# elasticNode.net
KiCad netlist of a schematic drawn in EAGLE
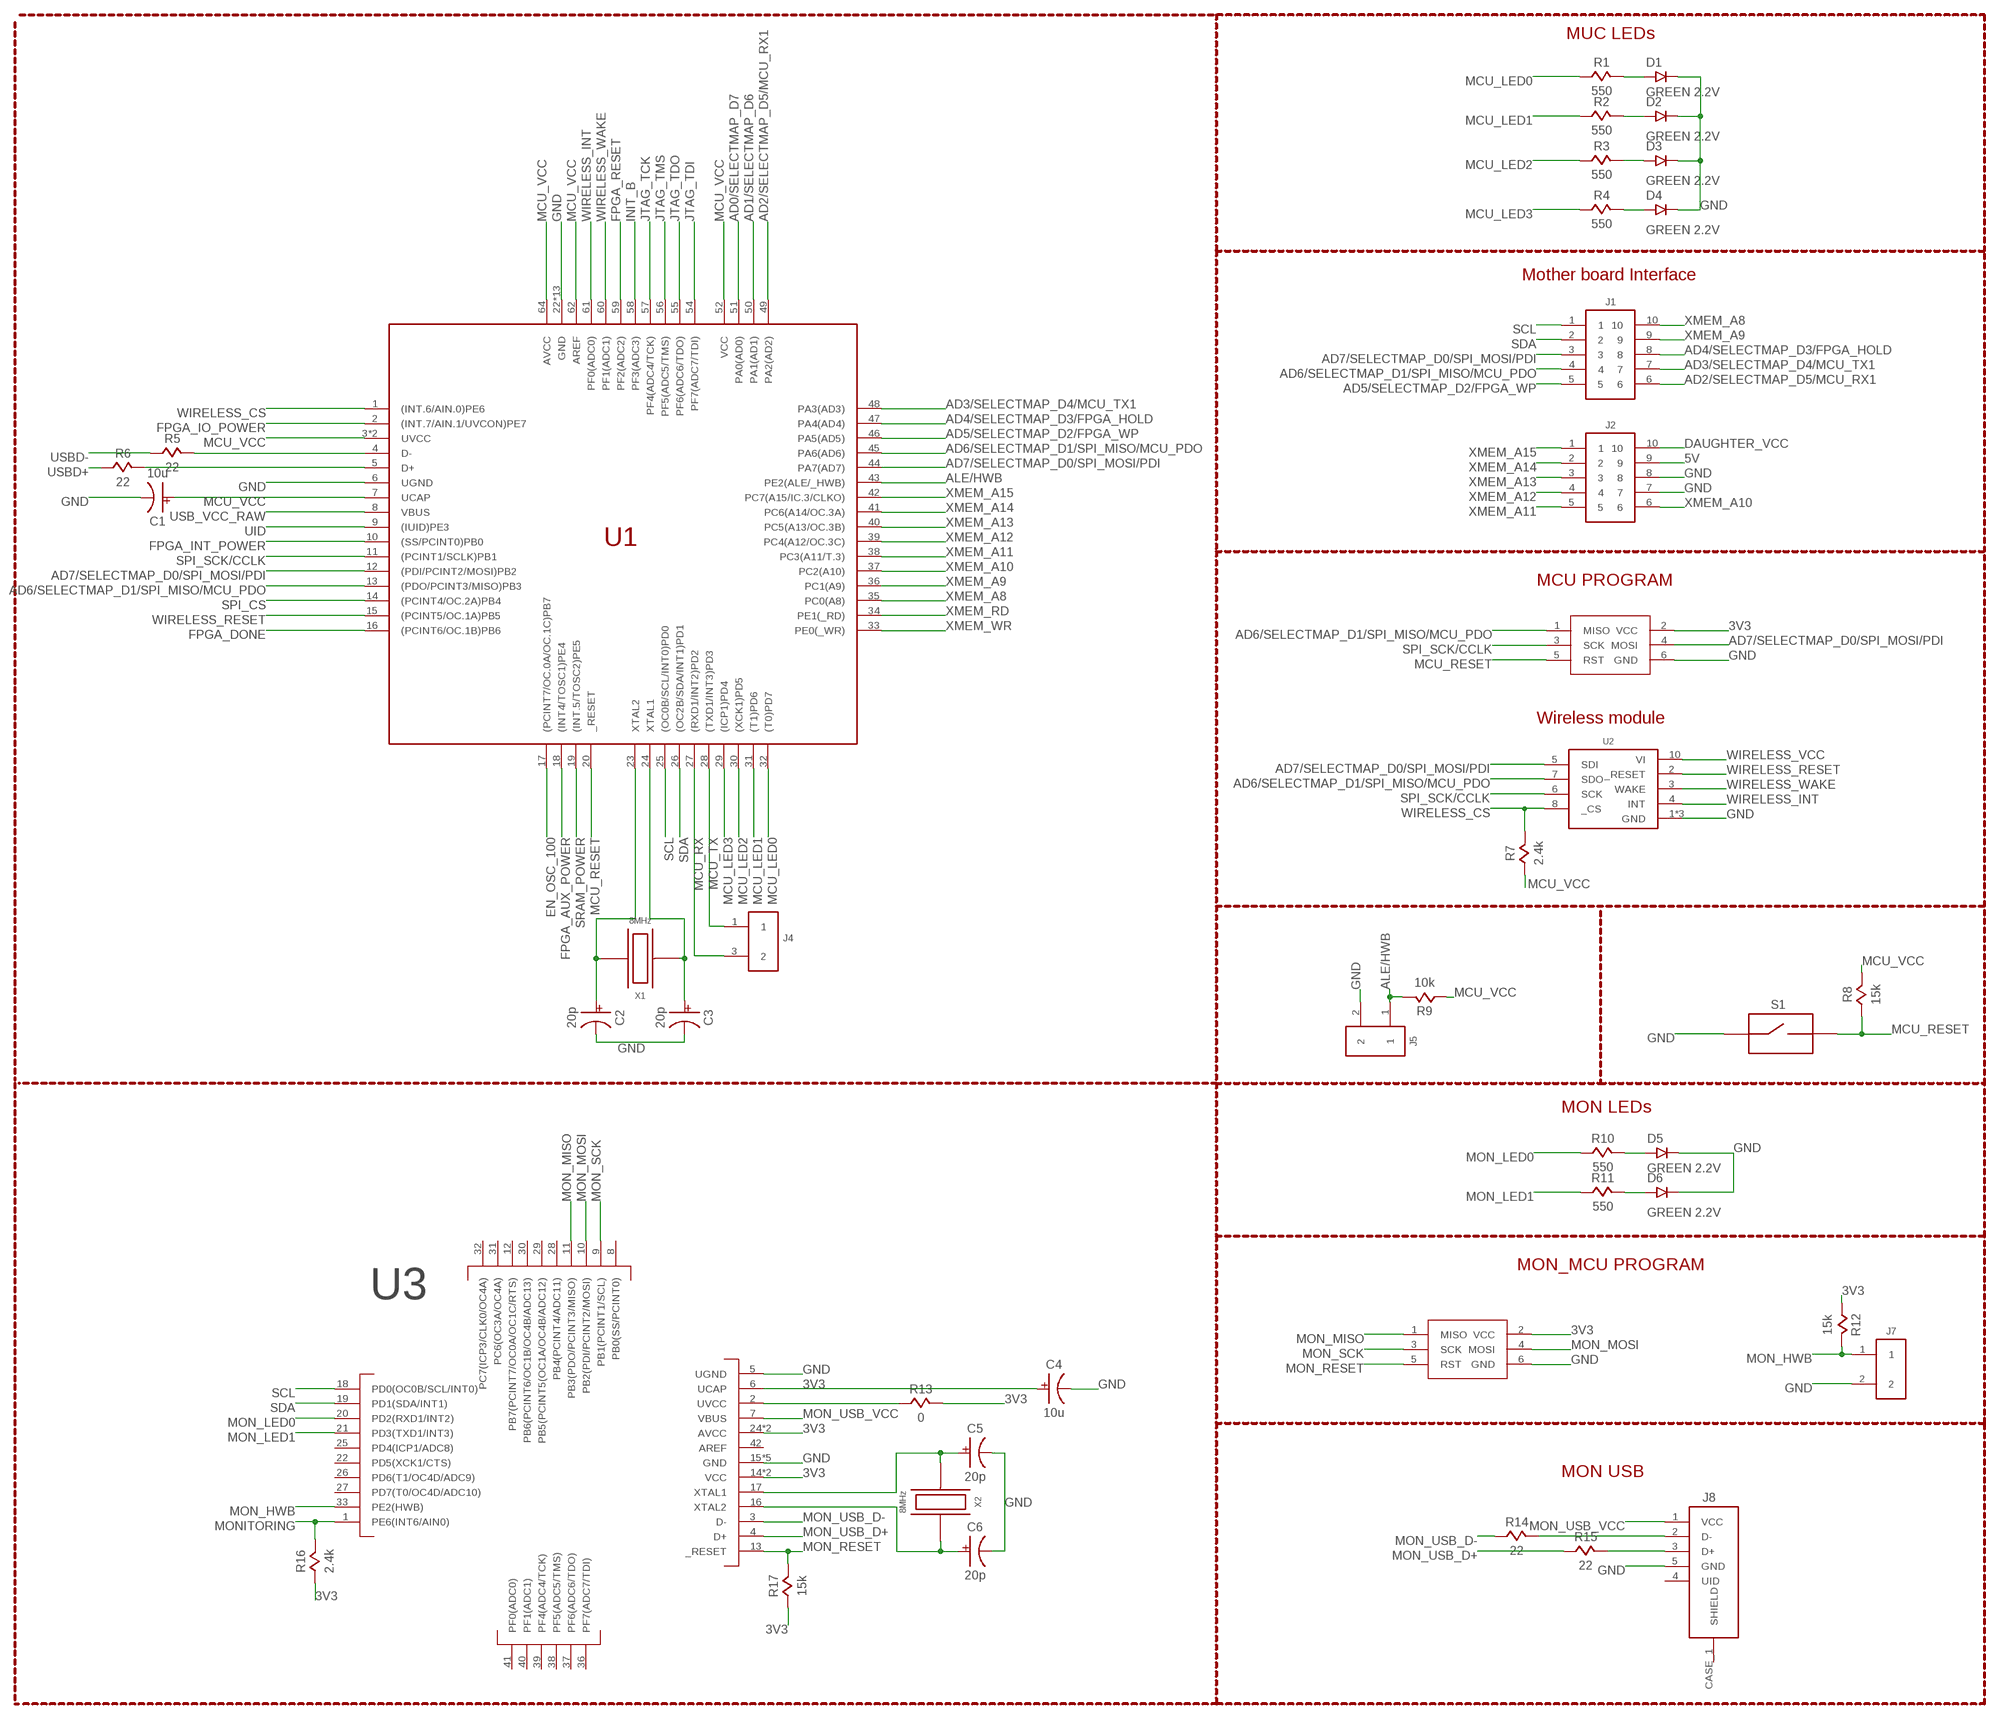
[diagram p0: schematic, sheet 1]
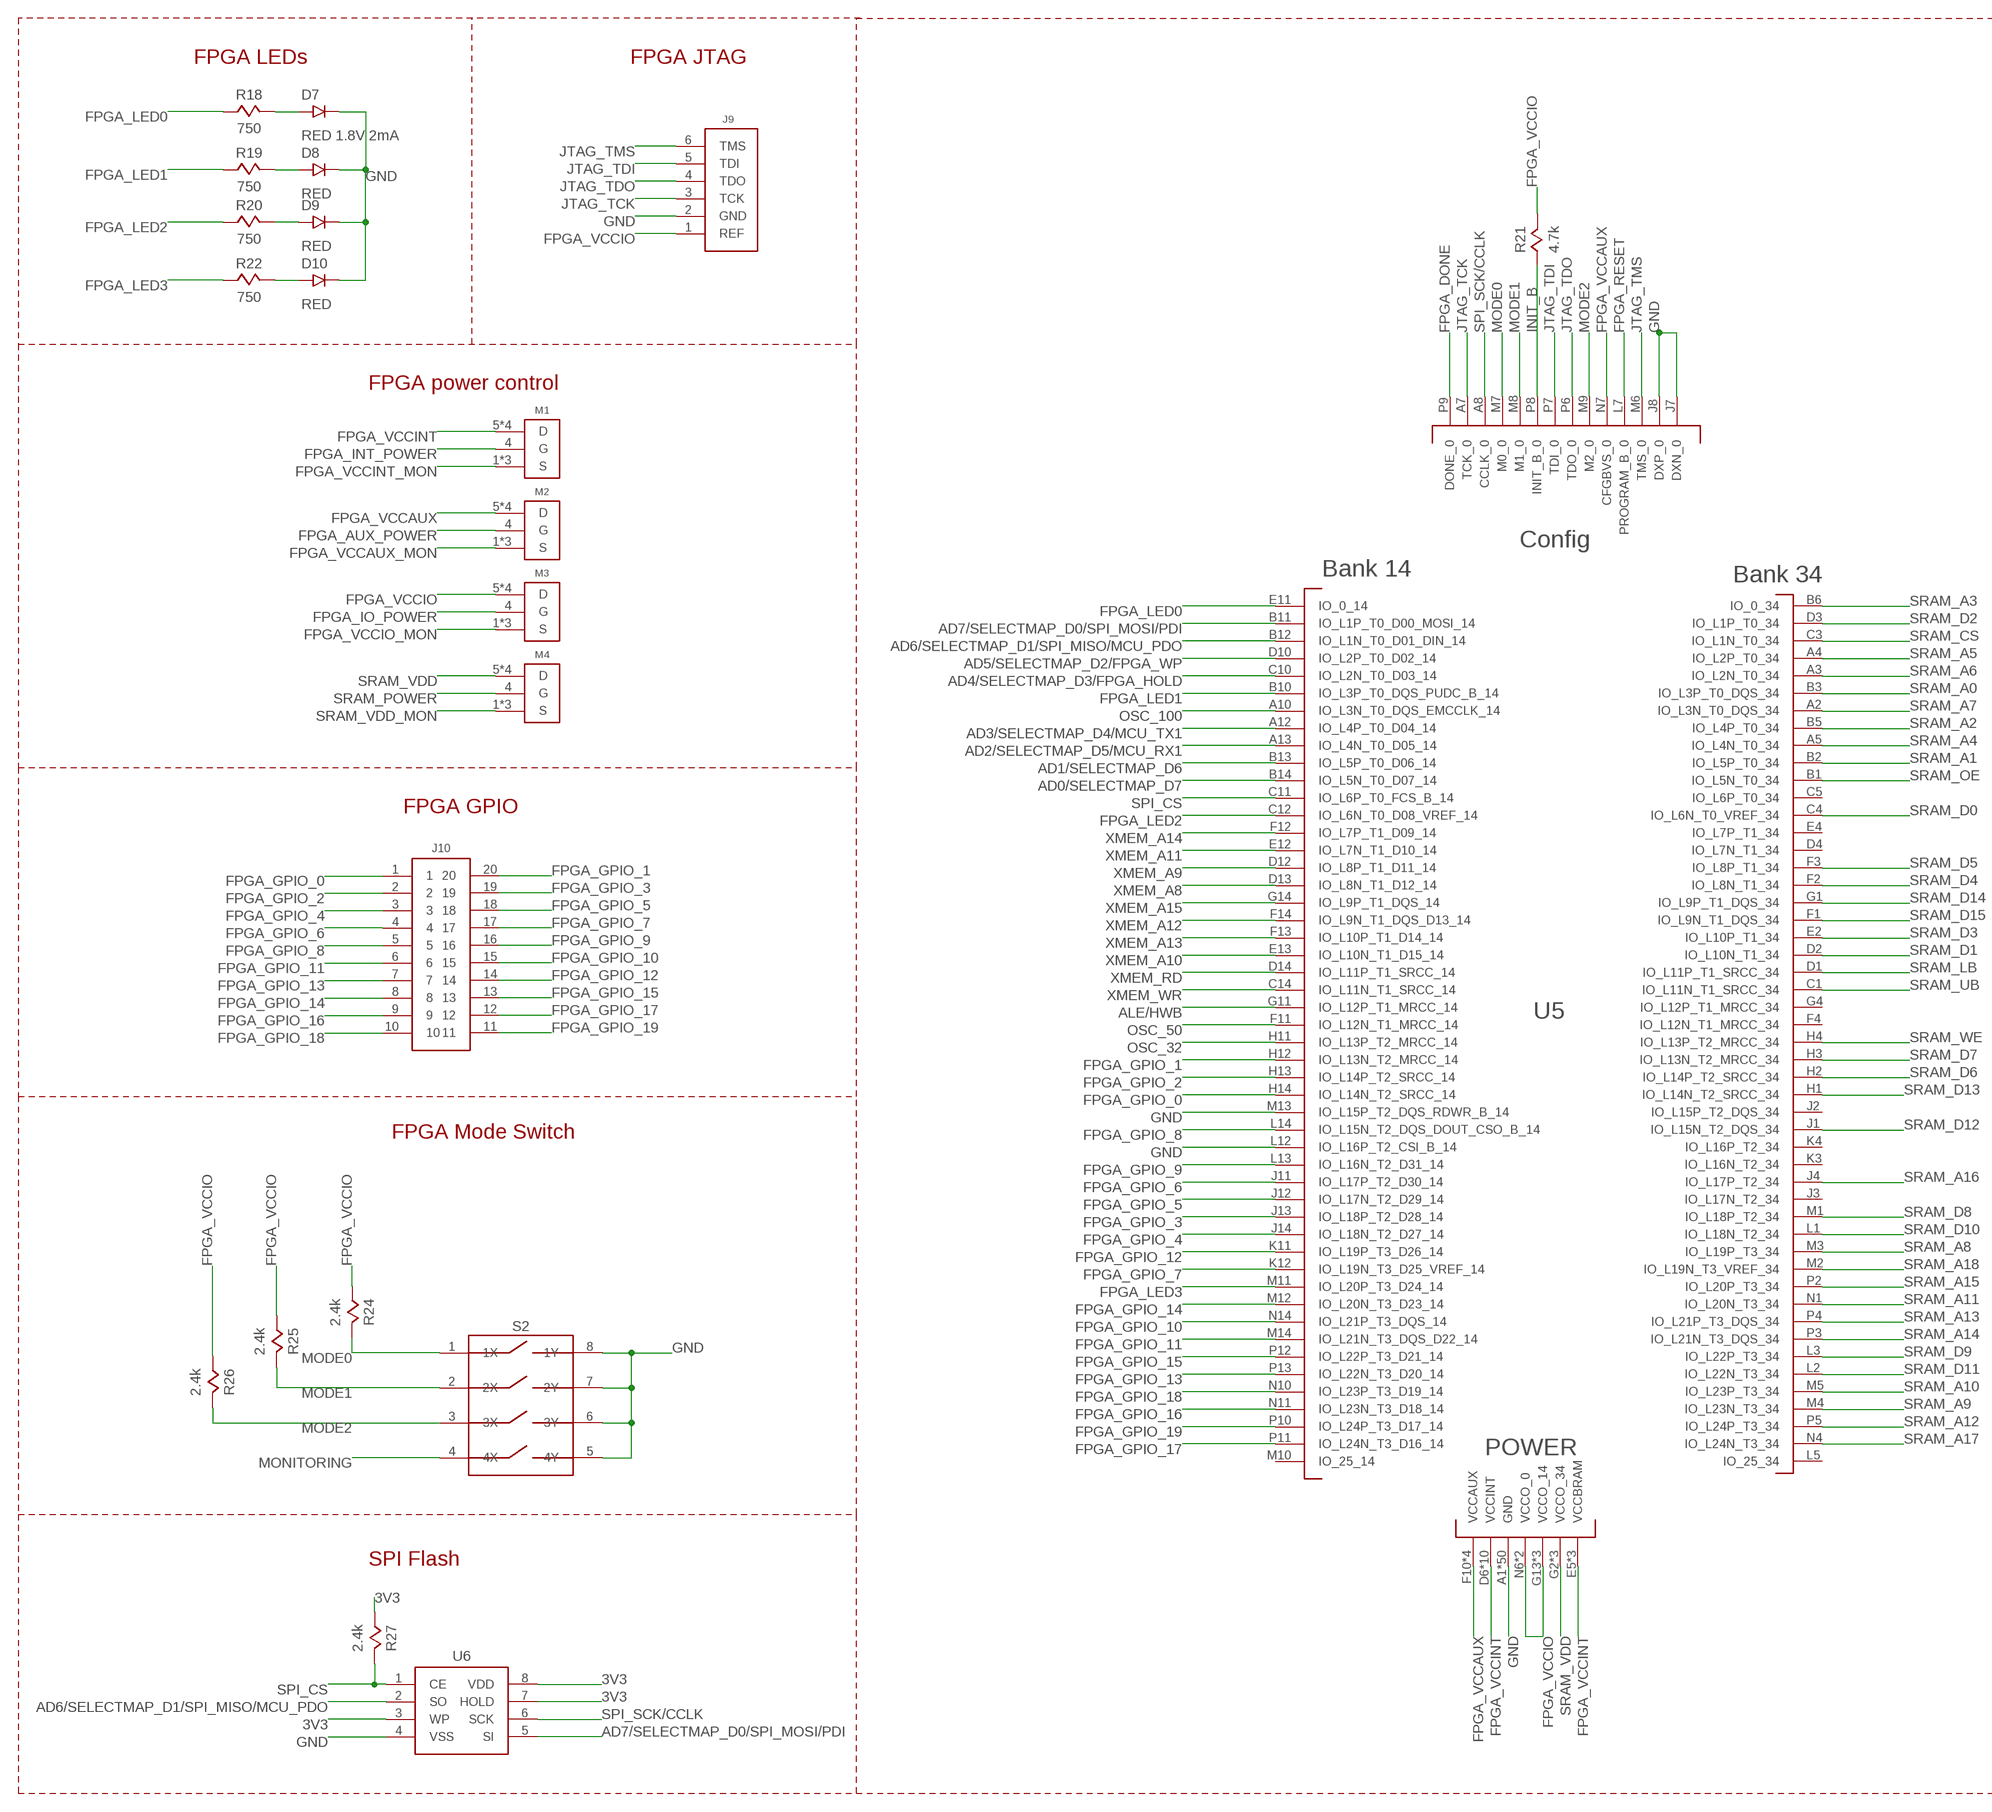
[diagram p1: schematic, sheet 2, part 1 of 2]
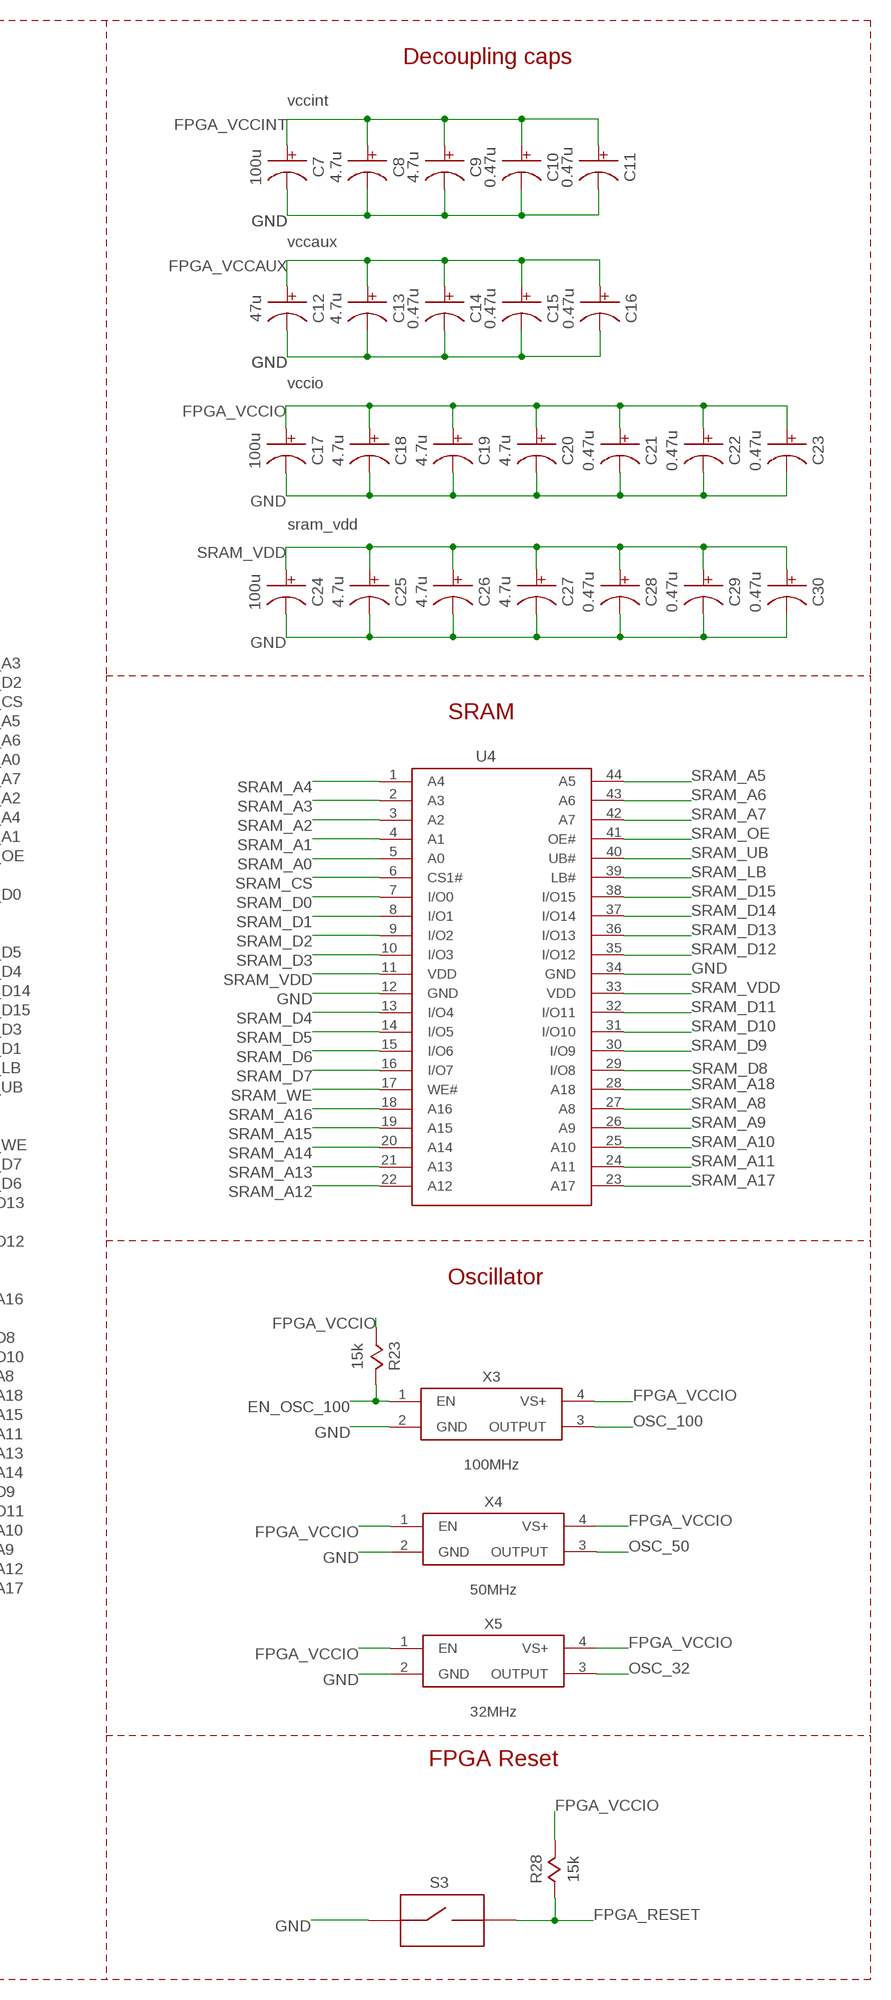
[diagram p2: schematic, sheet 2, part 2 of 2]
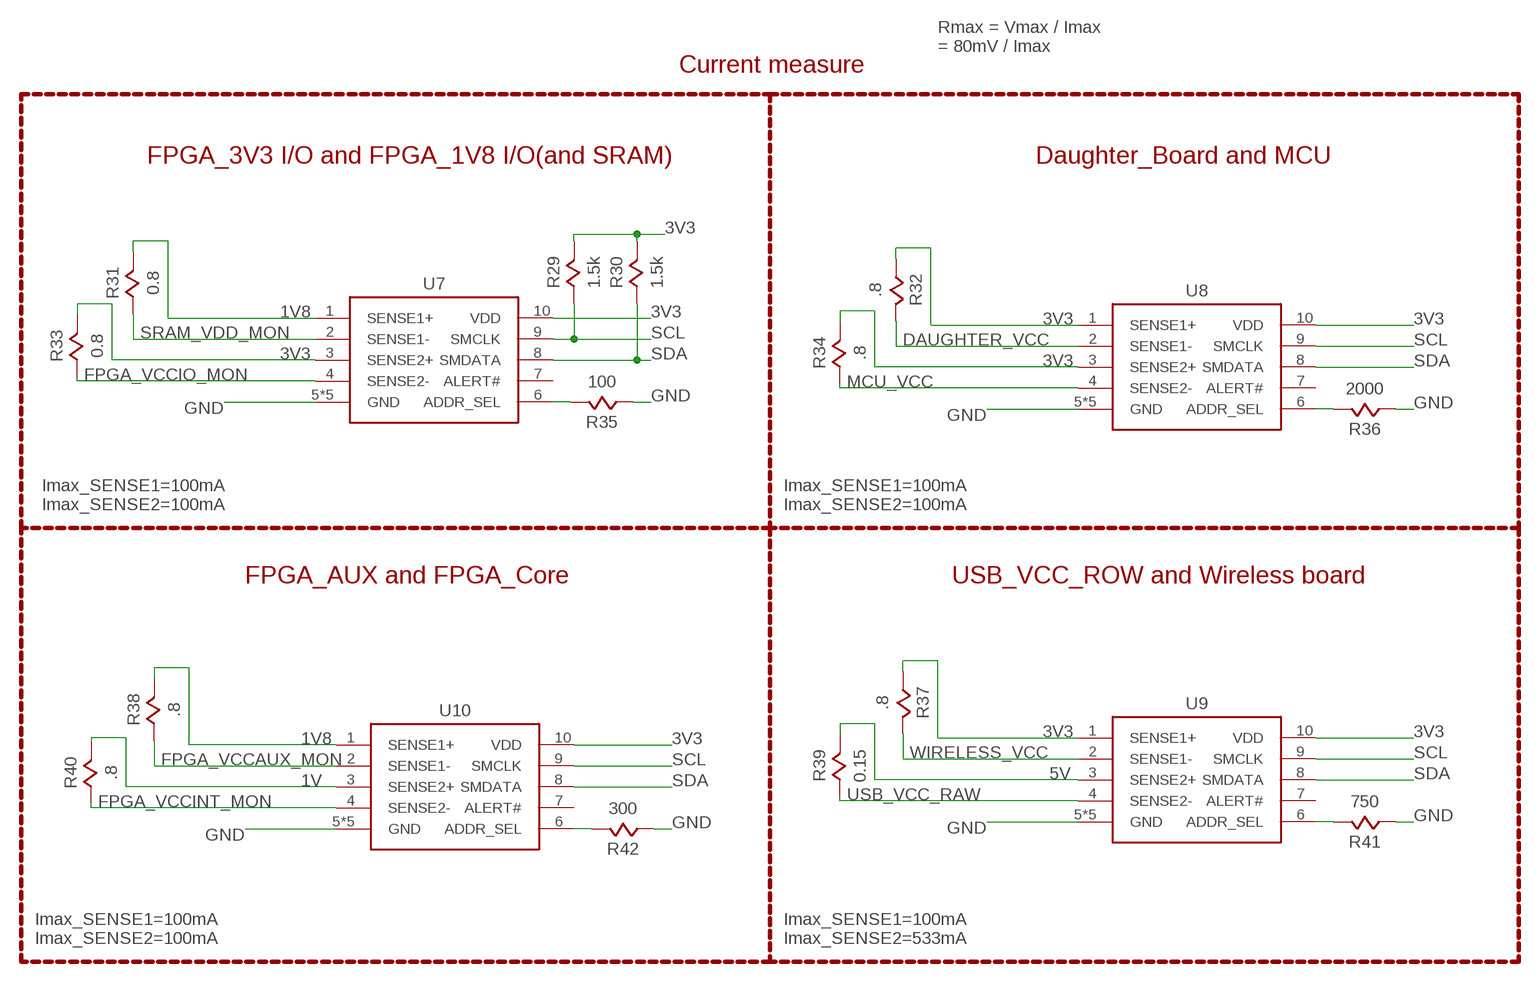
[diagram p3: schematic, sheet 3]
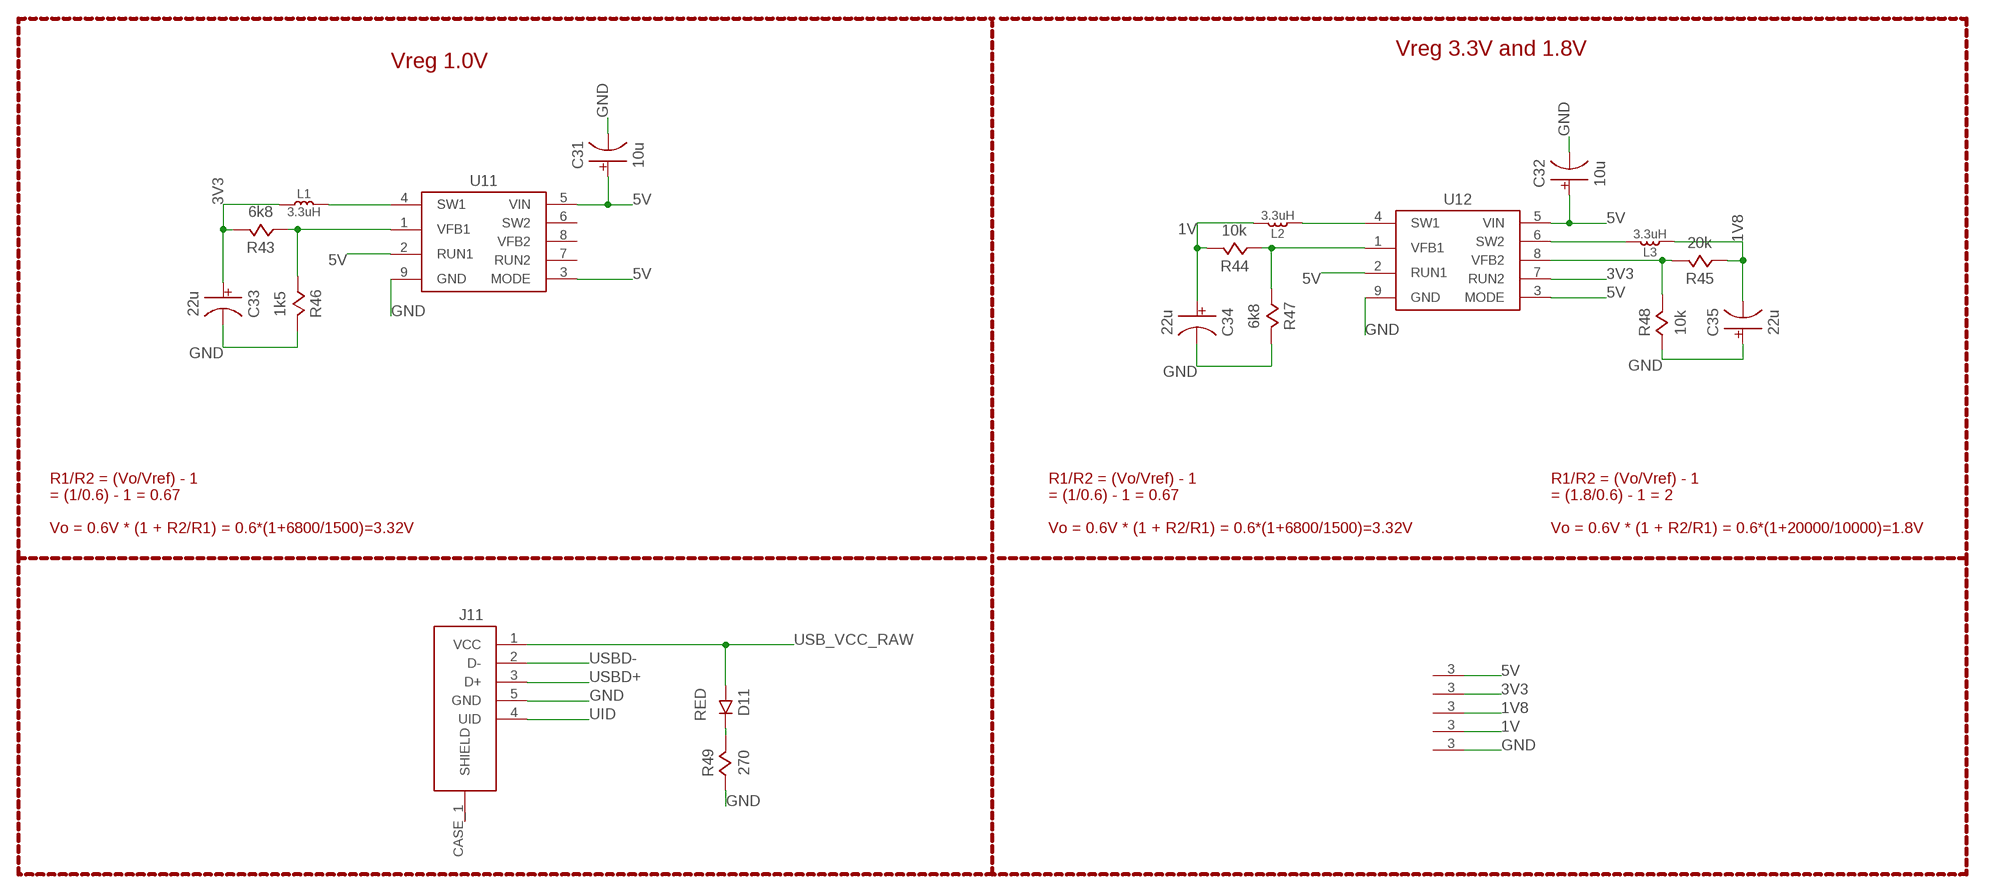
[diagram p4: schematic, sheet 4]

(export (version "E")
  (design (tool "Eeschema 10.0.6"))
  (components
    (comp (ref "C7")
      (value "100u")
      (footprint "eagle-import:1210")
      (libsource (lib "eagle-import") (part "CAPACITOR1210"))
    )
    (comp (ref "C8")
      (value "4.7u")
      (footprint "eagle-import:0805")
      (libsource (lib "eagle-import") (part "CAPACITOR0805"))
    )
    (comp (ref "C9")
      (value "4.7u")
      (footprint "eagle-import:0805")
      (libsource (lib "eagle-import") (part "CAPACITOR0805"))
    )
    (comp (ref "C10")
      (value "0.47u")
      (footprint "eagle-import:0805")
      (libsource (lib "eagle-import") (part "CAPACITOR0805"))
    )
    (comp (ref "C11")
      (value "0.47u")
      (footprint "eagle-import:0805")
      (libsource (lib "eagle-import") (part "CAPACITOR0805"))
    )
    (comp (ref "C12")
      (value "47u")
      (footprint "eagle-import:1210")
      (libsource (lib "eagle-import") (part "CAPACITOR1210"))
    )
    (comp (ref "C13")
      (value "4.7u")
      (footprint "eagle-import:0805")
      (libsource (lib "eagle-import") (part "CAPACITOR0805"))
    )
    (comp (ref "C14")
      (value "0.47u")
      (footprint "eagle-import:0805")
      (libsource (lib "eagle-import") (part "CAPACITOR0805"))
    )
    (comp (ref "C15")
      (value "0.47u")
      (footprint "eagle-import:0805")
      (libsource (lib "eagle-import") (part "CAPACITOR0805"))
    )
    (comp (ref "C16")
      (value "0.47u")
      (footprint "eagle-import:0805")
      (libsource (lib "eagle-import") (part "CAPACITOR0805"))
    )
    (comp (ref "C17")
      (value "100u")
      (footprint "eagle-import:1210")
      (libsource (lib "eagle-import") (part "CAPACITOR1210"))
    )
    (comp (ref "C18")
      (value "4.7u")
      (footprint "eagle-import:0805")
      (libsource (lib "eagle-import") (part "CAPACITOR0805"))
    )
    (comp (ref "C19")
      (value "4.7u")
      (footprint "eagle-import:0805")
      (libsource (lib "eagle-import") (part "CAPACITOR0805"))
    )
    (comp (ref "C20")
      (value "4.7u")
      (footprint "eagle-import:0805")
      (libsource (lib "eagle-import") (part "CAPACITOR0805"))
    )
    (comp (ref "C21")
      (value "0.47u")
      (footprint "eagle-import:0805")
      (libsource (lib "eagle-import") (part "CAPACITOR0805"))
    )
    (comp (ref "C22")
      (value "0.47u")
      (footprint "eagle-import:0805")
      (libsource (lib "eagle-import") (part "CAPACITOR0805"))
    )
    (comp (ref "C23")
      (value "0.47u")
      (footprint "eagle-import:0805")
      (libsource (lib "eagle-import") (part "CAPACITOR0805"))
    )
    (comp (ref "C24")
      (value "100u")
      (footprint "eagle-import:1210")
      (libsource (lib "eagle-import") (part "CAPACITOR1210"))
    )
    (comp (ref "C25")
      (value "4.7u")
      (footprint "eagle-import:0805")
      (libsource (lib "eagle-import") (part "CAPACITOR0805"))
    )
    (comp (ref "C26")
      (value "4.7u")
      (footprint "eagle-import:0805")
      (libsource (lib "eagle-import") (part "CAPACITOR0805"))
    )
    (comp (ref "C27")
      (value "4.7u")
      (footprint "eagle-import:0805")
      (libsource (lib "eagle-import") (part "CAPACITOR0805"))
    )
    (comp (ref "C28")
      (value "0.47u")
      (footprint "eagle-import:0805")
      (libsource (lib "eagle-import") (part "CAPACITOR0805"))
    )
    (comp (ref "C29")
      (value "0.47u")
      (footprint "eagle-import:0805")
      (libsource (lib "eagle-import") (part "CAPACITOR0805"))
    )
    (comp (ref "C30")
      (value "0.47u")
      (footprint "eagle-import:0805")
      (libsource (lib "eagle-import") (part "CAPACITOR0805"))
    )
    (comp (ref "D7")
      (value "RED 1.8V 2mA")
      (footprint "eagle-import:0805")
      (libsource (lib "eagle-import") (part "LED"))
    )
    (comp (ref "D8")
      (value "RED")
      (footprint "eagle-import:0805")
      (libsource (lib "eagle-import") (part "LED"))
    )
    (comp (ref "D9")
      (value "RED")
      (footprint "eagle-import:0805")
      (libsource (lib "eagle-import") (part "LED"))
    )
    (comp (ref "D10")
      (value "RED")
      (footprint "eagle-import:0805")
      (libsource (lib "eagle-import") (part "LED"))
    )
    (comp (ref "J9")
      (value "JTAG_CONN_6PINSMT")
      (footprint "eagle-import:6X1_JTAG")
      (libsource (lib "eagle-import") (part "JTAG_CONN_6PINSMT"))
    )
    (comp (ref "J10")
      (value "FEMALE_HEADER_10X2")
      (footprint "eagle-import:10X2_HEADER_SMT")
      (libsource (lib "eagle-import") (part "FEMALE_HEADER_10X2"))
    )
    (comp (ref "M1")
      (value "SISS23DN")
      (footprint "eagle-import:POWERPAK1212-8")
      (libsource (lib "eagle-import") (part "SISS23DN"))
    )
    (comp (ref "M2")
      (value "SISS23DN")
      (footprint "eagle-import:POWERPAK1212-8")
      (libsource (lib "eagle-import") (part "SISS23DN"))
    )
    (comp (ref "M3")
      (value "SISS23DN")
      (footprint "eagle-import:POWERPAK1212-8")
      (libsource (lib "eagle-import") (part "SISS23DN"))
    )
    (comp (ref "M4")
      (value "SISS23DN")
      (footprint "eagle-import:POWERPAK1212-8")
      (libsource (lib "eagle-import") (part "SISS23DN"))
    )
    (comp (ref "R18")
      (value "750")
      (footprint "eagle-import:0805")
      (libsource (lib "eagle-import") (part "RESISTOR"))
    )
    (comp (ref "R19")
      (value "750")
      (footprint "eagle-import:0805")
      (libsource (lib "eagle-import") (part "RESISTOR"))
    )
    (comp (ref "R20")
      (value "750")
      (footprint "eagle-import:0805")
      (libsource (lib "eagle-import") (part "RESISTOR"))
    )
    (comp (ref "R21")
      (value "4.7k")
      (footprint "eagle-import:0805")
      (libsource (lib "eagle-import") (part "RESISTOR"))
    )
    (comp (ref "R22")
      (value "750")
      (footprint "eagle-import:0805")
      (libsource (lib "eagle-import") (part "RESISTOR"))
    )
    (comp (ref "R23")
      (value "15k")
      (footprint "eagle-import:0805")
      (libsource (lib "eagle-import") (part "RESISTOR"))
    )
    (comp (ref "R24")
      (value "2.4k")
      (footprint "eagle-import:0805")
      (libsource (lib "eagle-import") (part "RESISTOR"))
    )
    (comp (ref "R25")
      (value "2.4k")
      (footprint "eagle-import:0805")
      (libsource (lib "eagle-import") (part "RESISTOR"))
    )
    (comp (ref "R26")
      (value "2.4k")
      (footprint "eagle-import:0805")
      (libsource (lib "eagle-import") (part "RESISTOR"))
    )
    (comp (ref "R27")
      (value "2.4k")
      (footprint "eagle-import:0805")
      (libsource (lib "eagle-import") (part "RESISTOR"))
    )
    (comp (ref "R28")
      (value "15k")
      (footprint "eagle-import:0805")
      (libsource (lib "eagle-import") (part "RESISTOR"))
    )
    (comp (ref "S2")
      (value "SPST_DIP_4")
      (footprint "eagle-import:SPST_DIP4_SMT")
      (libsource (lib "eagle-import") (part "SPST_DIP_4"))
    )
    (comp (ref "S3")
      (value "SPST_BUTTON2PIN_SMT")
      (footprint "eagle-import:SPST_2PIN_SMT")
      (libsource (lib "eagle-import") (part "SPST_BUTTON2PIN_SMT"))
    )
    (comp (ref "U4")
      (value "IS66WV51216EALL")
      (footprint "eagle-import:TSOP44")
      (libsource (lib "eagle-import") (part "IS66WV51216EALL"))
    )
    (comp (ref "U5")
      (value "SPARTAN7-LX15")
      (footprint "eagle-import:FTGB196")
      (libsource (lib "eagle-import") (part "SPARTAN7-LX15"))
    )
    (comp (ref "U6")
      (value "SST26VF032BWDFN")
      (footprint "eagle-import:WDFN8")
      (libsource (lib "eagle-import") (part "SST26VF032BWDFN"))
    )
    (comp (ref "X3")
      (value "100MHz")
      (footprint "eagle-import:3.2X2.5_OSC")
      (libsource (lib "eagle-import") (part "OSCILLATOR3.2X2.5"))
    )
    (comp (ref "X4")
      (value "50MHz")
      (footprint "eagle-import:3.2X2.5_OSC")
      (libsource (lib "eagle-import") (part "OSCILLATOR3.2X2.5"))
    )
    (comp (ref "X5")
      (value "32MHz")
      (footprint "eagle-import:3.2X2.5_OSC")
      (libsource (lib "eagle-import") (part "OSCILLATOR3.2X2.5"))
    )
    (comp (ref "R29")
      (value "1.5k")
      (footprint "eagle-import:0805")
      (libsource (lib "eagle-import") (part "RESISTOR"))
    )
    (comp (ref "R30")
      (value "1.5k")
      (footprint "eagle-import:0805")
      (libsource (lib "eagle-import") (part "RESISTOR"))
    )
    (comp (ref "R31")
      (value "0.8")
      (footprint "eagle-import:0805")
      (libsource (lib "eagle-import") (part "RESISTOR"))
    )
    (comp (ref "R32")
      (value ".8")
      (footprint "eagle-import:0805")
      (libsource (lib "eagle-import") (part "RESISTOR"))
    )
    (comp (ref "R33")
      (value "0.8")
      (footprint "eagle-import:0805")
      (libsource (lib "eagle-import") (part "RESISTOR"))
    )
    (comp (ref "R34")
      (value ".8")
      (footprint "eagle-import:0805")
      (libsource (lib "eagle-import") (part "RESISTOR"))
    )
    (comp (ref "R35")
      (value "100")
      (footprint "eagle-import:0805")
      (libsource (lib "eagle-import") (part "RESISTOR"))
    )
    (comp (ref "R36")
      (value "2000")
      (footprint "eagle-import:0805")
      (libsource (lib "eagle-import") (part "RESISTOR"))
    )
    (comp (ref "R37")
      (value ".8")
      (footprint "eagle-import:0805")
      (libsource (lib "eagle-import") (part "RESISTOR"))
    )
    (comp (ref "R38")
      (value ".8")
      (footprint "eagle-import:0805")
      (libsource (lib "eagle-import") (part "RESISTOR"))
    )
    (comp (ref "R39")
      (value "0.15")
      (footprint "eagle-import:0805")
      (libsource (lib "eagle-import") (part "RESISTOR"))
    )
    (comp (ref "R40")
      (value ".8")
      (footprint "eagle-import:0805")
      (libsource (lib "eagle-import") (part "RESISTOR"))
    )
    (comp (ref "R41")
      (value "750")
      (footprint "eagle-import:0805")
      (libsource (lib "eagle-import") (part "RESISTOR"))
    )
    (comp (ref "R42")
      (value "300")
      (footprint "eagle-import:0805")
      (libsource (lib "eagle-import") (part "RESISTOR"))
    )
    (comp (ref "U7")
      (value "PAC1720")
      (footprint "eagle-import:VDFN10")
      (libsource (lib "eagle-import") (part "PAC1720"))
    )
    (comp (ref "U8")
      (value "PAC1720")
      (footprint "eagle-import:VDFN10")
      (libsource (lib "eagle-import") (part "PAC1720"))
    )
    (comp (ref "U9")
      (value "PAC1720")
      (footprint "eagle-import:VDFN10")
      (libsource (lib "eagle-import") (part "PAC1720"))
    )
    (comp (ref "U10")
      (value "PAC1720")
      (footprint "eagle-import:VDFN10")
      (libsource (lib "eagle-import") (part "PAC1720"))
    )
    (comp (ref "C1")
      (value "10u")
      (footprint "eagle-import:0805")
      (libsource (lib "eagle-import") (part "CAPACITOR0805"))
    )
    (comp (ref "C2")
      (value "20p")
      (footprint "eagle-import:0805")
      (libsource (lib "eagle-import") (part "CAPACITOR0805"))
    )
    (comp (ref "C3")
      (value "20p")
      (footprint "eagle-import:0805")
      (libsource (lib "eagle-import") (part "CAPACITOR0805"))
    )
    (comp (ref "C4")
      (value "10u")
      (footprint "eagle-import:0805")
      (libsource (lib "eagle-import") (part "CAPACITOR0805"))
    )
    (comp (ref "C5")
      (value "20p")
      (footprint "eagle-import:0805")
      (libsource (lib "eagle-import") (part "CAPACITOR0805"))
    )
    (comp (ref "C6")
      (value "20p")
      (footprint "eagle-import:0805")
      (libsource (lib "eagle-import") (part "CAPACITOR0805"))
    )
    (comp (ref "D1")
      (value "GREEN 2.2V")
      (footprint "eagle-import:0805")
      (libsource (lib "eagle-import") (part "LED"))
    )
    (comp (ref "D2")
      (value "GREEN 2.2V")
      (footprint "eagle-import:0805")
      (libsource (lib "eagle-import") (part "LED"))
    )
    (comp (ref "D3")
      (value "GREEN 2.2V")
      (footprint "eagle-import:0805")
      (libsource (lib "eagle-import") (part "LED"))
    )
    (comp (ref "D4")
      (value "GREEN 2.2V")
      (footprint "eagle-import:0805")
      (libsource (lib "eagle-import") (part "LED"))
    )
    (comp (ref "D5")
      (value "GREEN 2.2V")
      (footprint "eagle-import:0805")
      (libsource (lib "eagle-import") (part "LED"))
    )
    (comp (ref "D6")
      (value "GREEN 2.2V")
      (footprint "eagle-import:0805")
      (libsource (lib "eagle-import") (part "LED"))
    )
    (comp (ref "J1")
      (value "FEMALE_HEADER_5X2")
      (footprint "eagle-import:5X2_HEADER_SMT_1.27")
      (libsource (lib "eagle-import") (part "FEMALE_HEADER_5X2"))
    )
    (comp (ref "J2")
      (value "FEMALE_HEADER_5X2")
      (footprint "eagle-import:5X2_HEADER_SMT_1.27")
      (libsource (lib "eagle-import") (part "FEMALE_HEADER_5X2"))
    )
    (comp (ref "J3")
      (value "ISP_CONN_6PIN")
      (footprint "eagle-import:ICSP_SMT")
      (fields (field (name "SPICEPREFIX") "X"))
      (libsource (lib "eagle-import") (part "ISP_CONN_6PIN"))
    )
    (comp (ref "J4")
      (value "FEMALE_HEADER_2X1")
      (footprint "eagle-import:2X1_HEADER")
      (libsource (lib "eagle-import") (part "FEMALE_HEADER_2X1"))
    )
    (comp (ref "J5")
      (value "JUMPER")
      (footprint "eagle-import:JUMPER_SMT")
      (libsource (lib "eagle-import") (part "JUMPER"))
    )
    (comp (ref "J6")
      (value "ISP_CONN_6PIN")
      (footprint "eagle-import:ICSP_SMT")
      (libsource (lib "eagle-import") (part "ISP_CONN_6PIN"))
    )
    (comp (ref "J7")
      (value "JUMPER")
      (footprint "eagle-import:JUMPER_SMT")
      (libsource (lib "eagle-import") (part "JUMPER"))
    )
    (comp (ref "J8")
      (value "USB_CONNMICRO_SMT")
      (footprint "eagle-import:USB_MICRO_B_SMT")
      (libsource (lib "eagle-import") (part "USB_CONNMICRO_SMT"))
    )
    (comp (ref "R1")
      (value "550")
      (footprint "eagle-import:0805")
      (libsource (lib "eagle-import") (part "RESISTOR"))
    )
    (comp (ref "R2")
      (value "550")
      (footprint "eagle-import:0805")
      (libsource (lib "eagle-import") (part "RESISTOR"))
    )
    (comp (ref "R3")
      (value "550")
      (footprint "eagle-import:0805")
      (libsource (lib "eagle-import") (part "RESISTOR"))
    )
    (comp (ref "R4")
      (value "550")
      (footprint "eagle-import:0805")
      (libsource (lib "eagle-import") (part "RESISTOR"))
    )
    (comp (ref "R5")
      (value "22")
      (footprint "eagle-import:0805")
      (libsource (lib "eagle-import") (part "RESISTOR"))
    )
    (comp (ref "R6")
      (value "22")
      (footprint "eagle-import:0805")
      (libsource (lib "eagle-import") (part "RESISTOR"))
    )
    (comp (ref "R7")
      (value "2.4k")
      (footprint "eagle-import:0805")
      (libsource (lib "eagle-import") (part "RESISTOR"))
    )
    (comp (ref "R8")
      (value "15k")
      (footprint "eagle-import:0805")
      (libsource (lib "eagle-import") (part "RESISTOR"))
    )
    (comp (ref "R9")
      (value "10k")
      (footprint "eagle-import:0805")
      (libsource (lib "eagle-import") (part "RESISTOR"))
    )
    (comp (ref "R10")
      (value "550")
      (footprint "eagle-import:0805")
      (libsource (lib "eagle-import") (part "RESISTOR"))
    )
    (comp (ref "R11")
      (value "550")
      (footprint "eagle-import:0805")
      (libsource (lib "eagle-import") (part "RESISTOR"))
    )
    (comp (ref "R12")
      (value "15k")
      (footprint "eagle-import:0805")
      (libsource (lib "eagle-import") (part "RESISTOR"))
    )
    (comp (ref "R13")
      (value "0")
      (footprint "eagle-import:0805")
      (libsource (lib "eagle-import") (part "RESISTOR"))
    )
    (comp (ref "R14")
      (value "22")
      (footprint "eagle-import:0805")
      (libsource (lib "eagle-import") (part "RESISTOR"))
    )
    (comp (ref "R15")
      (value "22")
      (footprint "eagle-import:0805")
      (libsource (lib "eagle-import") (part "RESISTOR"))
    )
    (comp (ref "R16")
      (value "2.4k")
      (footprint "eagle-import:0805")
      (libsource (lib "eagle-import") (part "RESISTOR"))
    )
    (comp (ref "R17")
      (value "15k")
      (footprint "eagle-import:0805")
      (libsource (lib "eagle-import") (part "RESISTOR"))
    )
    (comp (ref "S1")
      (value "SPST_BUTTON2PIN_SMT")
      (footprint "eagle-import:SPST_2PIN_SMT")
      (libsource (lib "eagle-import") (part "SPST_BUTTON2PIN_SMT"))
    )
    (comp (ref "U1")
      (value "AT90USB128")
      (footprint "eagle-import:QFN64")
      (libsource (lib "eagle-import") (part "AT90USB128"))
    )
    (comp (ref "U2")
      (value "MRF24J40MA")
      (footprint "eagle-import:MRF24J40MA")
      (libsource (lib "eagle-import") (part "MRF24J40MA"))
    )
    (comp (ref "U3")
      (value "ATMEGA32U4QFN")
      (footprint "eagle-import:QFN44")
      (libsource (lib "eagle-import") (part "ATMEGA32U4QFN"))
    )
    (comp (ref "X1")
      (value "8MHz")
      (footprint "eagle-import:3.2X2.5_OSC")
      (libsource (lib "eagle-import") (part "QUARTZ"))
    )
    (comp (ref "X2")
      (value "8MHz")
      (footprint "eagle-import:3.2X2.5_OSC")
      (libsource (lib "eagle-import") (part "QUARTZ"))
    )
    (comp (ref "C31")
      (value "10u")
      (footprint "eagle-import:0805")
      (libsource (lib "eagle-import") (part "CAPACITOR0805"))
    )
    (comp (ref "C32")
      (value "10u")
      (footprint "eagle-import:0805")
      (libsource (lib "eagle-import") (part "CAPACITOR0805"))
    )
    (comp (ref "C33")
      (value "22u")
      (footprint "eagle-import:0805")
      (libsource (lib "eagle-import") (part "CAPACITOR0805"))
    )
    (comp (ref "C34")
      (value "22u")
      (footprint "eagle-import:0805")
      (libsource (lib "eagle-import") (part "CAPACITOR0805"))
    )
    (comp (ref "C35")
      (value "22u")
      (footprint "eagle-import:0805")
      (libsource (lib "eagle-import") (part "CAPACITOR0805"))
    )
    (comp (ref "D11")
      (value "RED")
      (footprint "eagle-import:0805")
      (libsource (lib "eagle-import") (part "LED"))
    )
    (comp (ref "J11")
      (value "USB_CONNMICRO_SMT")
      (footprint "eagle-import:USB_MICRO_B_SMT")
      (libsource (lib "eagle-import") (part "USB_CONNMICRO_SMT"))
    )
    (comp (ref "L1")
      (value "3.3uH")
      (footprint "eagle-import:0805")
      (libsource (lib "eagle-import") (part "INDUCTOR"))
    )
    (comp (ref "L2")
      (value "3.3uH")
      (footprint "eagle-import:0805")
      (libsource (lib "eagle-import") (part "INDUCTOR"))
    )
    (comp (ref "L3")
      (value "3.3uH")
      (footprint "eagle-import:0805")
      (libsource (lib "eagle-import") (part "INDUCTOR"))
    )
    (comp (ref "R43")
      (value "6k8")
      (footprint "eagle-import:0805")
      (libsource (lib "eagle-import") (part "RESISTOR"))
    )
    (comp (ref "R44")
      (value "10k")
      (footprint "eagle-import:0805")
      (libsource (lib "eagle-import") (part "RESISTOR"))
    )
    (comp (ref "R45")
      (value "20k")
      (footprint "eagle-import:0805")
      (libsource (lib "eagle-import") (part "RESISTOR"))
    )
    (comp (ref "R46")
      (value "1k5")
      (footprint "eagle-import:0805")
      (libsource (lib "eagle-import") (part "RESISTOR"))
    )
    (comp (ref "R47")
      (value "6k8")
      (footprint "eagle-import:0805")
      (libsource (lib "eagle-import") (part "RESISTOR"))
    )
    (comp (ref "R48")
      (value "10k")
      (footprint "eagle-import:0805")
      (libsource (lib "eagle-import") (part "RESISTOR"))
    )
    (comp (ref "R49")
      (value "270")
      (footprint "eagle-import:0805")
      (libsource (lib "eagle-import") (part "RESISTOR"))
    )
    (comp (ref "TP1")
      (value "TEST_POINTTHT")
      (footprint "eagle-import:THT")
      (libsource (lib "eagle-import") (part "TEST_POINTTHT"))
    )
    (comp (ref "TP2")
      (value "TEST_POINTTHT")
      (footprint "eagle-import:THT")
      (libsource (lib "eagle-import") (part "TEST_POINTTHT"))
    )
    (comp (ref "TP3")
      (value "TEST_POINTTHT")
      (footprint "eagle-import:THT")
      (libsource (lib "eagle-import") (part "TEST_POINTTHT"))
    )
    (comp (ref "TP4")
      (value "TEST_POINTTHT")
      (footprint "eagle-import:THT")
      (libsource (lib "eagle-import") (part "TEST_POINTTHT"))
    )
    (comp (ref "TP5")
      (value "TEST_POINTTHT")
      (footprint "eagle-import:THT")
      (libsource (lib "eagle-import") (part "TEST_POINTTHT"))
    )
    (comp (ref "U11")
      (value "LTC3419DFN")
      (footprint "eagle-import:DFN8")
      (libsource (lib "eagle-import") (part "LTC3419DFN"))
    )
    (comp (ref "U12")
      (value "LTC3419DFN")
      (footprint "eagle-import:DFN8")
      (libsource (lib "eagle-import") (part "LTC3419DFN"))
    )
  )
  (nets
    (net (code "1") (name "1V") (class "Default")
      (node (ref "C34") (pin "1") (pinfunction "P$1_1") (pintype "bidirectional"))
      (node (ref "L2") (pin "2") (pinfunction "P$2_2") (pintype "bidirectional"))
      (node (ref "R40") (pin "2") (pinfunction "2_2") (pintype "bidirectional"))
      (node (ref "R44") (pin "2") (pinfunction "2_2") (pintype "bidirectional"))
      (node (ref "TP4") (pin "3") (pinfunction ">NAME_3") (pintype "bidirectional"))
      (node (ref "U10") (pin "3") (pinfunction "SENSE2+_3") (pintype "bidirectional"))
    )
    (net (code "2") (name "1V8") (class "Default")
      (node (ref "C35") (pin "2") (pinfunction "P$2_2") (pintype "bidirectional"))
      (node (ref "L3") (pin "1") (pinfunction "P$1_1") (pintype "bidirectional"))
      (node (ref "R31") (pin "2") (pinfunction "2_2") (pintype "bidirectional"))
      (node (ref "R38") (pin "2") (pinfunction "2_2") (pintype "bidirectional"))
      (node (ref "R45") (pin "1") (pinfunction "1_1") (pintype "bidirectional"))
      (node (ref "TP3") (pin "3") (pinfunction ">NAME_3") (pintype "bidirectional"))
      (node (ref "U10") (pin "1") (pinfunction "SENSE1+_1") (pintype "bidirectional"))
      (node (ref "U7") (pin "1") (pinfunction "SENSE1+_1") (pintype "bidirectional"))
    )
    (net (code "3") (name "3V3") (class "Default")
      (node (ref "C33") (pin "1") (pinfunction "P$1_1") (pintype "bidirectional"))
      (node (ref "C4") (pin "1") (pinfunction "P$1_1") (pintype "bidirectional"))
      (node (ref "J3") (pin "2") (pinfunction "VCC_2") (pintype "bidirectional"))
      (node (ref "J6") (pin "2") (pinfunction "VCC_2") (pintype "bidirectional"))
      (node (ref "L1") (pin "1") (pinfunction "P$1_1") (pintype "bidirectional"))
      (node (ref "R12") (pin "1") (pinfunction "1_1") (pintype "bidirectional"))
      (node (ref "R13") (pin "2") (pinfunction "2_2") (pintype "bidirectional"))
      (node (ref "R16") (pin "1") (pinfunction "1_1") (pintype "bidirectional"))
      (node (ref "R17") (pin "1") (pinfunction "1_1") (pintype "bidirectional"))
      (node (ref "R27") (pin "1") (pinfunction "1_1") (pintype "bidirectional"))
      (node (ref "R29") (pin "2") (pinfunction "2_2") (pintype "bidirectional"))
      (node (ref "R30") (pin "2") (pinfunction "2_2") (pintype "bidirectional"))
      (node (ref "R32") (pin "2") (pinfunction "2_2") (pintype "bidirectional"))
      (node (ref "R33") (pin "2") (pinfunction "2_2") (pintype "bidirectional"))
      (node (ref "R34") (pin "2") (pinfunction "2_2") (pintype "bidirectional"))
      (node (ref "R37") (pin "2") (pinfunction "2_2") (pintype "bidirectional"))
      (node (ref "R43") (pin "2") (pinfunction "2_2") (pintype "bidirectional"))
      (node (ref "TP2") (pin "3") (pinfunction ">NAME_3") (pintype "bidirectional"))
      (node (ref "U10") (pin "10") (pinfunction "VDD_10") (pintype "bidirectional"))
      (node (ref "U12") (pin "7") (pinfunction "RUN2_7") (pintype "bidirectional"))
      (node (ref "U3") (pin "14") (pinfunction "VCC_14") (pintype "bidirectional"))
      (node (ref "U3") (pin "24") (pinfunction "AVCC_24") (pintype "bidirectional"))
      (node (ref "U3") (pin "34") (pinfunction "VCC_34") (pintype "bidirectional"))
      (node (ref "U3") (pin "44") (pinfunction "AVCC_44") (pintype "bidirectional"))
      (node (ref "U3") (pin "6") (pinfunction "UCAP_6") (pintype "bidirectional"))
      (node (ref "U6") (pin "3") (pinfunction "WP_3") (pintype "bidirectional"))
      (node (ref "U6") (pin "7") (pinfunction "HOLD_7") (pintype "bidirectional"))
      (node (ref "U6") (pin "8") (pinfunction "VDD_8") (pintype "bidirectional"))
      (node (ref "U7") (pin "10") (pinfunction "VDD_10") (pintype "bidirectional"))
      (node (ref "U7") (pin "3") (pinfunction "SENSE2+_3") (pintype "bidirectional"))
      (node (ref "U8") (pin "1") (pinfunction "SENSE1+_1") (pintype "bidirectional"))
      (node (ref "U8") (pin "10") (pinfunction "VDD_10") (pintype "bidirectional"))
      (node (ref "U8") (pin "3") (pinfunction "SENSE2+_3") (pintype "bidirectional"))
      (node (ref "U9") (pin "1") (pinfunction "SENSE1+_1") (pintype "bidirectional"))
      (node (ref "U9") (pin "10") (pinfunction "VDD_10") (pintype "bidirectional"))
    )
    (net (code "4") (name "5V") (class "Default")
      (node (ref "C31") (pin "1") (pinfunction "P$1_1") (pintype "bidirectional"))
      (node (ref "C32") (pin "1") (pinfunction "P$1_1") (pintype "bidirectional"))
      (node (ref "J2") (pin "9") (pinfunction "9_9") (pintype "bidirectional"))
      (node (ref "R39") (pin "2") (pinfunction "2_2") (pintype "bidirectional"))
      (node (ref "TP1") (pin "3") (pinfunction ">NAME_3") (pintype "bidirectional"))
      (node (ref "U11") (pin "2") (pinfunction "RUN1_2") (pintype "bidirectional"))
      (node (ref "U11") (pin "3") (pinfunction "MODE_3") (pintype "bidirectional"))
      (node (ref "U11") (pin "5") (pinfunction "VIN_5") (pintype "bidirectional"))
      (node (ref "U12") (pin "2") (pinfunction "RUN1_2") (pintype "bidirectional"))
      (node (ref "U12") (pin "3") (pinfunction "MODE_3") (pintype "bidirectional"))
      (node (ref "U12") (pin "5") (pinfunction "VIN_5") (pintype "bidirectional"))
      (node (ref "U9") (pin "3") (pinfunction "SENSE2+_3") (pintype "bidirectional"))
    )
    (net (code "5") (name "AD0{slash}SELECTMAP_D7") (class "Default")
      (node (ref "U1") (pin "51") (pinfunction "PA0(AD0)_51") (pintype "bidirectional"))
      (node (ref "U5") (pin "B14") (pinfunction "IO_L5N_T0_D07_14_B14") (pintype "bidirectional"))
    )
    (net (code "6") (name "AD1{slash}SELECTMAP_D6") (class "Default")
      (node (ref "U1") (pin "50") (pinfunction "PA1(AD1)_50") (pintype "bidirectional"))
      (node (ref "U5") (pin "B13") (pinfunction "IO_L5P_T0_D06_14_B13") (pintype "bidirectional"))
    )
    (net (code "7") (name "AD2{slash}SELECTMAP_D5{slash}MCU_RX1") (class "Default")
      (node (ref "J1") (pin "6") (pinfunction "6_6") (pintype "bidirectional"))
      (node (ref "U1") (pin "49") (pinfunction "PA2(AD2)_49") (pintype "bidirectional"))
      (node (ref "U5") (pin "A13") (pinfunction "IO_L4N_T0_D05_14_A13") (pintype "bidirectional"))
    )
    (net (code "8") (name "AD3{slash}SELECTMAP_D4{slash}MCU_TX1") (class "Default")
      (node (ref "J1") (pin "7") (pinfunction "7_7") (pintype "bidirectional"))
      (node (ref "U1") (pin "48") (pinfunction "PA3(AD3)_48") (pintype "bidirectional"))
      (node (ref "U5") (pin "A12") (pinfunction "IO_L4P_T0_D04_14_A12") (pintype "bidirectional"))
    )
    (net (code "9") (name "AD4{slash}SELECTMAP_D3{slash}FPGA_HOLD") (class "Default")
      (node (ref "J1") (pin "8") (pinfunction "8_8") (pintype "bidirectional"))
      (node (ref "U1") (pin "47") (pinfunction "PA4(AD4)_47") (pintype "bidirectional"))
      (node (ref "U5") (pin "C10") (pinfunction "IO_L2N_T0_D03_14_C10") (pintype "bidirectional"))
    )
    (net (code "10") (name "AD5{slash}SELECTMAP_D2{slash}FPGA_WP") (class "Default")
      (node (ref "J1") (pin "5") (pinfunction "5_5") (pintype "bidirectional"))
      (node (ref "U1") (pin "46") (pinfunction "PA5(AD5)_46") (pintype "bidirectional"))
      (node (ref "U5") (pin "D10") (pinfunction "IO_L2P_T0_D02_14_D10") (pintype "bidirectional"))
    )
    (net (code "11") (name "AD6{slash}SELECTMAP_D1{slash}SPI_MISO{slash}MCU_PDO") (class "Default")
      (node (ref "J1") (pin "4") (pinfunction "4_4") (pintype "bidirectional"))
      (node (ref "J3") (pin "1") (pinfunction "MISO_1") (pintype "bidirectional"))
      (node (ref "U1") (pin "13") (pinfunction "(PDO/PCINT3/MISO)PB3_13") (pintype "bidirectional"))
      (node (ref "U1") (pin "45") (pinfunction "PA6(AD6)_45") (pintype "bidirectional"))
      (node (ref "U2") (pin "7") (pinfunction "SDO_7") (pintype "bidirectional"))
      (node (ref "U5") (pin "B12") (pinfunction "IO_L1N_T0_D01_DIN_14_B12") (pintype "bidirectional"))
      (node (ref "U6") (pin "2") (pinfunction "SO_2") (pintype "bidirectional"))
    )
    (net (code "12") (name "AD7{slash}SELECTMAP_D0{slash}SPI_MOSI{slash}PDI") (class "Default")
      (node (ref "J1") (pin "3") (pinfunction "3_3") (pintype "bidirectional"))
      (node (ref "J3") (pin "4") (pinfunction "MOSI_4") (pintype "bidirectional"))
      (node (ref "U1") (pin "12") (pinfunction "(PDI/PCINT2/MOSI)PB2_12") (pintype "bidirectional"))
      (node (ref "U1") (pin "44") (pinfunction "PA7(AD7)_44") (pintype "bidirectional"))
      (node (ref "U2") (pin "5") (pinfunction "SDI_5") (pintype "bidirectional"))
      (node (ref "U5") (pin "B11") (pinfunction "IO_L1P_T0_D00_MOSI_14_B11") (pintype "bidirectional"))
      (node (ref "U6") (pin "5") (pinfunction "SI_5") (pintype "bidirectional"))
    )
    (net (code "13") (name "ALE{slash}HWB") (class "Default")
      (node (ref "J5") (pin "1") (pinfunction "1_1") (pintype "bidirectional"))
      (node (ref "R9") (pin "2") (pinfunction "2_2") (pintype "bidirectional"))
      (node (ref "U1") (pin "43") (pinfunction "PE2(ALE/_HWB)_43") (pintype "bidirectional"))
      (node (ref "U5") (pin "G11") (pinfunction "IO_L12P_T1_MRCC_14_G11") (pintype "bidirectional"))
    )
    (net (code "14") (name "DAUGHTER_VCC") (class "Default")
      (node (ref "J2") (pin "10") (pinfunction "10_10") (pintype "bidirectional"))
      (node (ref "R32") (pin "1") (pinfunction "1_1") (pintype "bidirectional"))
      (node (ref "U8") (pin "2") (pinfunction "SENSE1-_2") (pintype "bidirectional"))
    )
    (net (code "15") (name "EN_OSC_100") (class "Default")
      (node (ref "R23") (pin "1") (pinfunction "1_1") (pintype "bidirectional"))
      (node (ref "U1") (pin "17") (pinfunction "(PCINT7/OC.0A/OC.1C)PB7_17") (pintype "bidirectional"))
      (node (ref "X3") (pin "1") (pinfunction "EN_1") (pintype "bidirectional"))
    )
    (net (code "16") (name "FPGA_AUX_POWER") (class "Default")
      (node (ref "M2") (pin "4") (pinfunction "G_4") (pintype "bidirectional"))
      (node (ref "U1") (pin "18") (pinfunction "(INT4/TOSC1)PE4_18") (pintype "bidirectional"))
    )
    (net (code "17") (name "FPGA_DONE") (class "Default")
      (node (ref "U1") (pin "16") (pinfunction "(PCINT6/OC.1B)PB6_16") (pintype "bidirectional"))
      (node (ref "U5") (pin "P9") (pinfunction "DONE_0_P9") (pintype "bidirectional"))
    )
    (net (code "18") (name "FPGA_GPIO_0") (class "Default")
      (node (ref "J10") (pin "1") (pinfunction "1_1") (pintype "bidirectional"))
      (node (ref "U5") (pin "H14") (pinfunction "IO_L14N_T2_SRCC_14_H14") (pintype "bidirectional"))
    )
    (net (code "19") (name "FPGA_GPIO_1") (class "Default")
      (node (ref "J10") (pin "20") (pinfunction "20_20") (pintype "bidirectional"))
      (node (ref "U5") (pin "H12") (pinfunction "IO_L13N_T2_MRCC_14_H12") (pintype "bidirectional"))
    )
    (net (code "20") (name "FPGA_GPIO_2") (class "Default")
      (node (ref "J10") (pin "2") (pinfunction "2_2") (pintype "bidirectional"))
      (node (ref "U5") (pin "H13") (pinfunction "IO_L14P_T2_SRCC_14_H13") (pintype "bidirectional"))
    )
    (net (code "21") (name "FPGA_GPIO_3") (class "Default")
      (node (ref "J10") (pin "19") (pinfunction "19_19") (pintype "bidirectional"))
      (node (ref "U5") (pin "J13") (pinfunction "IO_L18P_T2_D28_14_J13") (pintype "bidirectional"))
    )
    (net (code "22") (name "FPGA_GPIO_4") (class "Default")
      (node (ref "J10") (pin "3") (pinfunction "3_3") (pintype "bidirectional"))
      (node (ref "U5") (pin "J14") (pinfunction "IO_L18N_T2_D27_14_J14") (pintype "bidirectional"))
    )
    (net (code "23") (name "FPGA_GPIO_5") (class "Default")
      (node (ref "J10") (pin "18") (pinfunction "18_18") (pintype "bidirectional"))
      (node (ref "U5") (pin "J12") (pinfunction "IO_L17N_T2_D29_14_J12") (pintype "bidirectional"))
    )
    (net (code "24") (name "FPGA_GPIO_6") (class "Default")
      (node (ref "J10") (pin "4") (pinfunction "4_4") (pintype "bidirectional"))
      (node (ref "U5") (pin "J11") (pinfunction "IO_L17P_T2_D30_14_J11") (pintype "bidirectional"))
    )
    (net (code "25") (name "FPGA_GPIO_7") (class "Default")
      (node (ref "J10") (pin "17") (pinfunction "17_17") (pintype "bidirectional"))
      (node (ref "U5") (pin "K12") (pinfunction "IO_L19N_T3_D25_VREF_14_K12") (pintype "bidirectional"))
    )
    (net (code "26") (name "FPGA_GPIO_8") (class "Default")
      (node (ref "J10") (pin "5") (pinfunction "5_5") (pintype "bidirectional"))
      (node (ref "U5") (pin "L14") (pinfunction "IO_L15N_T2_DQS_DOUT_CSO_B_14_L14") (pintype "bidirectional"))
    )
    (net (code "27") (name "FPGA_GPIO_9") (class "Default")
      (node (ref "J10") (pin "16") (pinfunction "16_16") (pintype "bidirectional"))
      (node (ref "U5") (pin "L13") (pinfunction "IO_L16N_T2_D31_14_L13") (pintype "bidirectional"))
    )
    (net (code "28") (name "FPGA_GPIO_10") (class "Default")
      (node (ref "J10") (pin "15") (pinfunction "15_15") (pintype "bidirectional"))
      (node (ref "U5") (pin "N14") (pinfunction "IO_L21P_T3_DQS_14_N14") (pintype "bidirectional"))
    )
    (net (code "29") (name "FPGA_GPIO_11") (class "Default")
      (node (ref "J10") (pin "6") (pinfunction "6_6") (pintype "bidirectional"))
      (node (ref "U5") (pin "M14") (pinfunction "IO_L21N_T3_DQS_D22_14_M14") (pintype "bidirectional"))
    )
    (net (code "30") (name "FPGA_GPIO_12") (class "Default")
      (node (ref "J10") (pin "14") (pinfunction "14_14") (pintype "bidirectional"))
      (node (ref "U5") (pin "K11") (pinfunction "IO_L19P_T3_D26_14_K11") (pintype "bidirectional"))
    )
    (net (code "31") (name "FPGA_GPIO_13") (class "Default")
      (node (ref "J10") (pin "7") (pinfunction "7_7") (pintype "bidirectional"))
      (node (ref "U5") (pin "P13") (pinfunction "IO_L22N_T3_D20_14_P13") (pintype "bidirectional"))
    )
    (net (code "32") (name "FPGA_GPIO_14") (class "Default")
      (node (ref "J10") (pin "8") (pinfunction "8_8") (pintype "bidirectional"))
      (node (ref "U5") (pin "M12") (pinfunction "IO_L20N_T3_D23_14_M12") (pintype "bidirectional"))
    )
    (net (code "33") (name "FPGA_GPIO_15") (class "Default")
      (node (ref "J10") (pin "13") (pinfunction "13_13") (pintype "bidirectional"))
      (node (ref "U5") (pin "P12") (pinfunction "IO_L22P_T3_D21_14_P12") (pintype "bidirectional"))
    )
    (net (code "34") (name "FPGA_GPIO_16") (class "Default")
      (node (ref "J10") (pin "9") (pinfunction "9_9") (pintype "bidirectional"))
      (node (ref "U5") (pin "N11") (pinfunction "IO_L23N_T3_D18_14_N11") (pintype "bidirectional"))
    )
    (net (code "35") (name "FPGA_GPIO_17") (class "Default")
      (node (ref "J10") (pin "12") (pinfunction "12_12") (pintype "bidirectional"))
      (node (ref "U5") (pin "P11") (pinfunction "IO_L24N_T3_D16_14_P11") (pintype "bidirectional"))
    )
    (net (code "36") (name "FPGA_GPIO_18") (class "Default")
      (node (ref "J10") (pin "10") (pinfunction "10_10") (pintype "bidirectional"))
      (node (ref "U5") (pin "N10") (pinfunction "IO_L23P_T3_D19_14_N10") (pintype "bidirectional"))
    )
    (net (code "37") (name "FPGA_GPIO_19") (class "Default")
      (node (ref "J10") (pin "11") (pinfunction "11_11") (pintype "bidirectional"))
      (node (ref "U5") (pin "P10") (pinfunction "IO_L24P_T3_D17_14_P10") (pintype "bidirectional"))
    )
    (net (code "38") (name "FPGA_INT_POWER") (class "Default")
      (node (ref "M1") (pin "4") (pinfunction "G_4") (pintype "bidirectional"))
      (node (ref "U1") (pin "10") (pinfunction "(SS/PCINT0)PB0_10") (pintype "bidirectional"))
    )
    (net (code "39") (name "FPGA_IO_POWER") (class "Default")
      (node (ref "M3") (pin "4") (pinfunction "G_4") (pintype "bidirectional"))
      (node (ref "U1") (pin "2") (pinfunction "(INT.7/AIN.1/UVCON)PE7_2") (pintype "bidirectional"))
    )
    (net (code "40") (name "FPGA_LED0") (class "Default")
      (node (ref "R18") (pin "1") (pinfunction "1_1") (pintype "bidirectional"))
      (node (ref "U5") (pin "E11") (pinfunction "IO_0_14_E11") (pintype "bidirectional"))
    )
    (net (code "41") (name "FPGA_LED1") (class "Default")
      (node (ref "R19") (pin "1") (pinfunction "1_1") (pintype "bidirectional"))
      (node (ref "U5") (pin "B10") (pinfunction "IO_L3P_T0_DQS_PUDC_B_14_B10") (pintype "bidirectional"))
    )
    (net (code "42") (name "FPGA_LED2") (class "Default")
      (node (ref "R20") (pin "1") (pinfunction "1_1") (pintype "bidirectional"))
      (node (ref "U5") (pin "C12") (pinfunction "IO_L6N_T0_D08_VREF_14_C12") (pintype "bidirectional"))
    )
    (net (code "43") (name "FPGA_LED3") (class "Default")
      (node (ref "R22") (pin "1") (pinfunction "1_1") (pintype "bidirectional"))
      (node (ref "U5") (pin "M11") (pinfunction "IO_L20P_T3_D24_14_M11") (pintype "bidirectional"))
    )
    (net (code "44") (name "FPGA_RESET") (class "Default")
      (node (ref "R28") (pin "1") (pinfunction "1_1") (pintype "bidirectional"))
      (node (ref "S3") (pin "2") (pinfunction "3_2") (pintype "bidirectional"))
      (node (ref "U1") (pin "59") (pinfunction "PF2(ADC2)_59") (pintype "bidirectional"))
      (node (ref "U5") (pin "L7") (pinfunction "PROGRAM_B_0_L7") (pintype "bidirectional"))
    )
    (net (code "45") (name "FPGA_VCCAUX") (class "Default")
      (node (ref "C12") (pin "1") (pinfunction "P$1_1") (pintype "bidirectional"))
      (node (ref "C13") (pin "1") (pinfunction "P$1_1") (pintype "bidirectional"))
      (node (ref "C14") (pin "1") (pinfunction "P$1_1") (pintype "bidirectional"))
      (node (ref "C15") (pin "1") (pinfunction "P$1_1") (pintype "bidirectional"))
      (node (ref "C16") (pin "1") (pinfunction "P$1_1") (pintype "bidirectional"))
      (node (ref "M2") (pin "5") (pinfunction "D_5") (pintype "bidirectional"))
      (node (ref "M2") (pin "6") (pinfunction "D_6") (pintype "bidirectional"))
      (node (ref "M2") (pin "7") (pinfunction "D_7") (pintype "bidirectional"))
      (node (ref "M2") (pin "8") (pinfunction "D_8") (pintype "bidirectional"))
      (node (ref "U5") (pin "F10") (pinfunction "VCCAUX_F10") (pintype "bidirectional"))
      (node (ref "U5") (pin "H10") (pinfunction "VCCAUX_H10") (pintype "bidirectional"))
      (node (ref "U5") (pin "K10") (pinfunction "VCCAUX_K10") (pintype "bidirectional"))
      (node (ref "U5") (pin "L9") (pinfunction "VCCAUX_L9") (pintype "bidirectional"))
      (node (ref "U5") (pin "N7") (pinfunction "CFGBVS_0_N7") (pintype "bidirectional"))
    )
    (net (code "46") (name "FPGA_VCCAUX_MON") (class "Default")
      (node (ref "M2") (pin "1") (pinfunction "S_1") (pintype "bidirectional"))
      (node (ref "M2") (pin "2") (pinfunction "S_2") (pintype "bidirectional"))
      (node (ref "M2") (pin "3") (pinfunction "S_3") (pintype "bidirectional"))
      (node (ref "R38") (pin "1") (pinfunction "1_1") (pintype "bidirectional"))
      (node (ref "U10") (pin "2") (pinfunction "SENSE1-_2") (pintype "bidirectional"))
    )
    (net (code "47") (name "FPGA_VCCINT") (class "Default")
      (node (ref "C10") (pin "1") (pinfunction "P$1_1") (pintype "bidirectional"))
      (node (ref "C11") (pin "1") (pinfunction "P$1_1") (pintype "bidirectional"))
      (node (ref "C7") (pin "1") (pinfunction "P$1_1") (pintype "bidirectional"))
      (node (ref "C8") (pin "1") (pinfunction "P$1_1") (pintype "bidirectional"))
      (node (ref "C9") (pin "1") (pinfunction "P$1_1") (pintype "bidirectional"))
      (node (ref "M1") (pin "5") (pinfunction "D_5") (pintype "bidirectional"))
      (node (ref "M1") (pin "6") (pinfunction "D_6") (pintype "bidirectional"))
      (node (ref "M1") (pin "7") (pinfunction "D_7") (pintype "bidirectional"))
      (node (ref "M1") (pin "8") (pinfunction "D_8") (pintype "bidirectional"))
      (node (ref "U5") (pin "D6") (pinfunction "VCCINT_D6") (pintype "bidirectional"))
      (node (ref "U5") (pin "D8") (pinfunction "VCCINT_D8") (pintype "bidirectional"))
      (node (ref "U5") (pin "E5") (pinfunction "VCCBRAM_E5") (pintype "bidirectional"))
      (node (ref "U5") (pin "E7") (pinfunction "VCCINT_E7") (pintype "bidirectional"))
      (node (ref "U5") (pin "E9") (pinfunction "VCCINT_E9") (pintype "bidirectional"))
      (node (ref "U5") (pin "F6") (pinfunction "VCCINT_F6") (pintype "bidirectional"))
      (node (ref "U5") (pin "G5") (pinfunction "VCCBRAM_G5") (pintype "bidirectional"))
      (node (ref "U5") (pin "G9") (pinfunction "VCCINT_G9") (pintype "bidirectional"))
      (node (ref "U5") (pin "H6") (pinfunction "VCCINT_H6") (pintype "bidirectional"))
      (node (ref "U5") (pin "J5") (pinfunction "VCCBRAM_J5") (pintype "bidirectional"))
      (node (ref "U5") (pin "J9") (pinfunction "VCCINT_J9") (pintype "bidirectional"))
      (node (ref "U5") (pin "K6") (pinfunction "VCCINT_K6") (pintype "bidirectional"))
      (node (ref "U5") (pin "K8") (pinfunction "VCCINT_K8") (pintype "bidirectional"))
    )
    (net (code "48") (name "FPGA_VCCINT_MON") (class "Default")
      (node (ref "M1") (pin "1") (pinfunction "S_1") (pintype "bidirectional"))
      (node (ref "M1") (pin "2") (pinfunction "S_2") (pintype "bidirectional"))
      (node (ref "M1") (pin "3") (pinfunction "S_3") (pintype "bidirectional"))
      (node (ref "R40") (pin "1") (pinfunction "1_1") (pintype "bidirectional"))
      (node (ref "U10") (pin "4") (pinfunction "SENSE2-_4") (pintype "bidirectional"))
    )
    (net (code "49") (name "FPGA_VCCIO") (class "Default")
      (node (ref "C17") (pin "1") (pinfunction "P$1_1") (pintype "bidirectional"))
      (node (ref "C18") (pin "1") (pinfunction "P$1_1") (pintype "bidirectional"))
      (node (ref "C19") (pin "1") (pinfunction "P$1_1") (pintype "bidirectional"))
      (node (ref "C20") (pin "1") (pinfunction "P$1_1") (pintype "bidirectional"))
      (node (ref "C21") (pin "1") (pinfunction "P$1_1") (pintype "bidirectional"))
      (node (ref "C22") (pin "1") (pinfunction "P$1_1") (pintype "bidirectional"))
      (node (ref "C23") (pin "1") (pinfunction "P$1_1") (pintype "bidirectional"))
      (node (ref "J9") (pin "1") (pinfunction "REF_1") (pintype "bidirectional"))
      (node (ref "M3") (pin "5") (pinfunction "D_5") (pintype "bidirectional"))
      (node (ref "M3") (pin "6") (pinfunction "D_6") (pintype "bidirectional"))
      (node (ref "M3") (pin "7") (pinfunction "D_7") (pintype "bidirectional"))
      (node (ref "M3") (pin "8") (pinfunction "D_8") (pintype "bidirectional"))
      (node (ref "R21") (pin "2") (pinfunction "2_2") (pintype "bidirectional"))
      (node (ref "R23") (pin "2") (pinfunction "2_2") (pintype "bidirectional"))
      (node (ref "R24") (pin "1") (pinfunction "1_1") (pintype "bidirectional"))
      (node (ref "R25") (pin "1") (pinfunction "1_1") (pintype "bidirectional"))
      (node (ref "R26") (pin "1") (pinfunction "1_1") (pintype "bidirectional"))
      (node (ref "R28") (pin "2") (pinfunction "2_2") (pintype "bidirectional"))
      (node (ref "U5") (pin "G13") (pinfunction "VCCO_14_G13") (pintype "bidirectional"))
      (node (ref "U5") (pin "K13") (pinfunction "VCCO_14_K13") (pintype "bidirectional"))
      (node (ref "U5") (pin "N13") (pinfunction "VCCO_14_N13") (pintype "bidirectional"))
      (node (ref "U5") (pin "N6") (pinfunction "VCCO_0_N6") (pintype "bidirectional"))
      (node (ref "U5") (pin "N8") (pinfunction "VCCO_0_N8") (pintype "bidirectional"))
      (node (ref "X3") (pin "4") (pinfunction "VS+_4") (pintype "bidirectional"))
      (node (ref "X4") (pin "1") (pinfunction "EN_1") (pintype "bidirectional"))
      (node (ref "X4") (pin "4") (pinfunction "VS+_4") (pintype "bidirectional"))
      (node (ref "X5") (pin "1") (pinfunction "EN_1") (pintype "bidirectional"))
      (node (ref "X5") (pin "4") (pinfunction "VS+_4") (pintype "bidirectional"))
    )
    (net (code "50") (name "FPGA_VCCIO_MON") (class "Default")
      (node (ref "M3") (pin "1") (pinfunction "S_1") (pintype "bidirectional"))
      (node (ref "M3") (pin "2") (pinfunction "S_2") (pintype "bidirectional"))
      (node (ref "M3") (pin "3") (pinfunction "S_3") (pintype "bidirectional"))
      (node (ref "R33") (pin "1") (pinfunction "1_1") (pintype "bidirectional"))
      (node (ref "U7") (pin "4") (pinfunction "SENSE2-_4") (pintype "bidirectional"))
    )
    (net (code "51") (name "GND") (class "Default")
      (node (ref "C1") (pin "2") (pinfunction "P$2_2") (pintype "bidirectional"))
      (node (ref "C10") (pin "2") (pinfunction "P$2_2") (pintype "bidirectional"))
      (node (ref "C11") (pin "2") (pinfunction "P$2_2") (pintype "bidirectional"))
      (node (ref "C12") (pin "2") (pinfunction "P$2_2") (pintype "bidirectional"))
      (node (ref "C13") (pin "2") (pinfunction "P$2_2") (pintype "bidirectional"))
      (node (ref "C14") (pin "2") (pinfunction "P$2_2") (pintype "bidirectional"))
      (node (ref "C15") (pin "2") (pinfunction "P$2_2") (pintype "bidirectional"))
      (node (ref "C16") (pin "2") (pinfunction "P$2_2") (pintype "bidirectional"))
      (node (ref "C17") (pin "2") (pinfunction "P$2_2") (pintype "bidirectional"))
      (node (ref "C18") (pin "2") (pinfunction "P$2_2") (pintype "bidirectional"))
      (node (ref "C19") (pin "2") (pinfunction "P$2_2") (pintype "bidirectional"))
      (node (ref "C2") (pin "2") (pinfunction "P$2_2") (pintype "bidirectional"))
      (node (ref "C20") (pin "2") (pinfunction "P$2_2") (pintype "bidirectional"))
      (node (ref "C21") (pin "2") (pinfunction "P$2_2") (pintype "bidirectional"))
      (node (ref "C22") (pin "2") (pinfunction "P$2_2") (pintype "bidirectional"))
      (node (ref "C23") (pin "2") (pinfunction "P$2_2") (pintype "bidirectional"))
      (node (ref "C24") (pin "2") (pinfunction "P$2_2") (pintype "bidirectional"))
      (node (ref "C25") (pin "2") (pinfunction "P$2_2") (pintype "bidirectional"))
      (node (ref "C26") (pin "2") (pinfunction "P$2_2") (pintype "bidirectional"))
      (node (ref "C27") (pin "2") (pinfunction "P$2_2") (pintype "bidirectional"))
      (node (ref "C28") (pin "2") (pinfunction "P$2_2") (pintype "bidirectional"))
      (node (ref "C29") (pin "2") (pinfunction "P$2_2") (pintype "bidirectional"))
      (node (ref "C3") (pin "2") (pinfunction "P$2_2") (pintype "bidirectional"))
      (node (ref "C30") (pin "2") (pinfunction "P$2_2") (pintype "bidirectional"))
      (node (ref "C31") (pin "2") (pinfunction "P$2_2") (pintype "bidirectional"))
      (node (ref "C32") (pin "2") (pinfunction "P$2_2") (pintype "bidirectional"))
      (node (ref "C33") (pin "2") (pinfunction "P$2_2") (pintype "bidirectional"))
      (node (ref "C34") (pin "2") (pinfunction "P$2_2") (pintype "bidirectional"))
      (node (ref "C35") (pin "1") (pinfunction "P$1_1") (pintype "bidirectional"))
      (node (ref "C4") (pin "2") (pinfunction "P$2_2") (pintype "bidirectional"))
      (node (ref "C5") (pin "2") (pinfunction "P$2_2") (pintype "bidirectional"))
      (node (ref "C6") (pin "2") (pinfunction "P$2_2") (pintype "bidirectional"))
      (node (ref "C7") (pin "2") (pinfunction "P$2_2") (pintype "bidirectional"))
      (node (ref "C8") (pin "2") (pinfunction "P$2_2") (pintype "bidirectional"))
      (node (ref "C9") (pin "2") (pinfunction "P$2_2") (pintype "bidirectional"))
      (node (ref "D1") (pin "2") (pinfunction "2_2") (pintype "bidirectional"))
      (node (ref "D10") (pin "2") (pinfunction "2_2") (pintype "bidirectional"))
      (node (ref "D2") (pin "2") (pinfunction "2_2") (pintype "bidirectional"))
      (node (ref "D3") (pin "2") (pinfunction "2_2") (pintype "bidirectional"))
      (node (ref "D4") (pin "2") (pinfunction "2_2") (pintype "bidirectional"))
      (node (ref "D5") (pin "2") (pinfunction "2_2") (pintype "bidirectional"))
      (node (ref "D6") (pin "2") (pinfunction "2_2") (pintype "bidirectional"))
      (node (ref "D7") (pin "2") (pinfunction "2_2") (pintype "bidirectional"))
      (node (ref "D8") (pin "2") (pinfunction "2_2") (pintype "bidirectional"))
      (node (ref "D9") (pin "2") (pinfunction "2_2") (pintype "bidirectional"))
      (node (ref "J11") (pin "5") (pinfunction "GND_5") (pintype "bidirectional"))
      (node (ref "J2") (pin "7") (pinfunction "7_7") (pintype "bidirectional"))
      (node (ref "J2") (pin "8") (pinfunction "8_8") (pintype "bidirectional"))
      (node (ref "J3") (pin "6") (pinfunction "GND_6") (pintype "bidirectional"))
      (node (ref "J5") (pin "2") (pinfunction "2_2") (pintype "bidirectional"))
      (node (ref "J6") (pin "6") (pinfunction "GND_6") (pintype "bidirectional"))
      (node (ref "J7") (pin "2") (pinfunction "2_2") (pintype "bidirectional"))
      (node (ref "J8") (pin "5") (pinfunction "GND_5") (pintype "bidirectional"))
      (node (ref "J9") (pin "2") (pinfunction "GND_2") (pintype "bidirectional"))
      (node (ref "R35") (pin "1") (pinfunction "1_1") (pintype "bidirectional"))
      (node (ref "R36") (pin "1") (pinfunction "1_1") (pintype "bidirectional"))
      (node (ref "R41") (pin "1") (pinfunction "1_1") (pintype "bidirectional"))
      (node (ref "R42") (pin "1") (pinfunction "1_1") (pintype "bidirectional"))
      (node (ref "R46") (pin "2") (pinfunction "2_2") (pintype "bidirectional"))
      (node (ref "R47") (pin "2") (pinfunction "2_2") (pintype "bidirectional"))
      (node (ref "R48") (pin "1") (pinfunction "1_1") (pintype "bidirectional"))
      (node (ref "R49") (pin "1") (pinfunction "1_1") (pintype "bidirectional"))
      (node (ref "S1") (pin "1") (pinfunction "1_1") (pintype "bidirectional"))
      (node (ref "S2") (pin "5") (pinfunction "4Y_5") (pintype "bidirectional"))
      (node (ref "S2") (pin "6") (pinfunction "3Y_6") (pintype "bidirectional"))
      (node (ref "S2") (pin "7") (pinfunction "2Y_7") (pintype "bidirectional"))
      (node (ref "S2") (pin "8") (pinfunction "1Y_8") (pintype "bidirectional"))
      (node (ref "S3") (pin "1") (pinfunction "1_1") (pintype "bidirectional"))
      (node (ref "TP5") (pin "3") (pinfunction ">NAME_3") (pintype "bidirectional"))
      (node (ref "U1") (pin "22") (pinfunction "GND_22") (pintype "bidirectional"))
      (node (ref "U1") (pin "53") (pinfunction "GND_53") (pintype "bidirectional"))
      (node (ref "U1") (pin "6") (pinfunction "UGND_6") (pintype "bidirectional"))
      (node (ref "U1") (pin "63") (pinfunction "GND_63") (pintype "bidirectional"))
      (node (ref "U1") (pin "PAD") (pinfunction "GND_PAD") (pintype "bidirectional"))
      (node (ref "U1") (pin "VIA1") (pinfunction "GND_VIA1") (pintype "bidirectional"))
      (node (ref "U1") (pin "VIA2") (pinfunction "GND_VIA2") (pintype "bidirectional"))
      (node (ref "U1") (pin "VIA3") (pinfunction "GND_VIA3") (pintype "bidirectional"))
      (node (ref "U1") (pin "VIA4") (pinfunction "GND_VIA4") (pintype "bidirectional"))
      (node (ref "U1") (pin "VIA5") (pinfunction "GND_VIA5") (pintype "bidirectional"))
      (node (ref "U1") (pin "VIA6") (pinfunction "GND_VIA6") (pintype "bidirectional"))
      (node (ref "U1") (pin "VIA7") (pinfunction "GND_VIA7") (pintype "bidirectional"))
      (node (ref "U1") (pin "VIA8") (pinfunction "GND_VIA8") (pintype "bidirectional"))
      (node (ref "U1") (pin "VIA9") (pinfunction "GND_VIA9") (pintype "bidirectional"))
      (node (ref "U10") (pin "5") (pinfunction "GND_5") (pintype "bidirectional"))
      (node (ref "U10") (pin "P$1") (pinfunction "GND_P$1") (pintype "bidirectional"))
      (node (ref "U10") (pin "P$2") (pinfunction "GND_P$2") (pintype "bidirectional"))
      (node (ref "U10") (pin "P$3") (pinfunction "GND_P$3") (pintype "bidirectional"))
      (node (ref "U10") (pin "P$4") (pinfunction "GND_P$4") (pintype "bidirectional"))
      (node (ref "U11") (pin "9") (pinfunction "GND_9") (pintype "bidirectional"))
      (node (ref "U12") (pin "9") (pinfunction "GND_9") (pintype "bidirectional"))
      (node (ref "U2") (pin "1") (pinfunction "GND_1") (pintype "bidirectional"))
      (node (ref "U2") (pin "11") (pinfunction "GND_11") (pintype "bidirectional"))
      (node (ref "U2") (pin "12") (pinfunction "GND_12") (pintype "bidirectional"))
      (node (ref "U3") (pin "15") (pinfunction "GND_15") (pintype "bidirectional"))
      (node (ref "U3") (pin "23") (pinfunction "GND_23") (pintype "bidirectional"))
      (node (ref "U3") (pin "35") (pinfunction "GND_35") (pintype "bidirectional"))
      (node (ref "U3") (pin "43") (pinfunction "GND_43") (pintype "bidirectional"))
      (node (ref "U3") (pin "45") (pinfunction "GND_45") (pintype "bidirectional"))
      (node (ref "U3") (pin "5") (pinfunction "UGND_5") (pintype "bidirectional"))
      (node (ref "U4") (pin "12") (pinfunction "GND_12") (pintype "bidirectional"))
      (node (ref "U4") (pin "34") (pinfunction "GND_34") (pintype "bidirectional"))
      (node (ref "U5") (pin "A1") (pinfunction "GND_A1") (pintype "bidirectional"))
      (node (ref "U5") (pin "A11") (pinfunction "GND_A11") (pintype "bidirectional"))
      (node (ref "U5") (pin "A14") (pinfunction "GND_A14") (pintype "bidirectional"))
      (node (ref "U5") (pin "A6") (pinfunction "GND_A6") (pintype "bidirectional"))
      (node (ref "U5") (pin "A9") (pinfunction "GND_A9") (pintype "bidirectional"))
      (node (ref "U5") (pin "B4") (pinfunction "GND_B4") (pintype "bidirectional"))
      (node (ref "U5") (pin "B7") (pinfunction "GND_B7") (pintype "bidirectional"))
      (node (ref "U5") (pin "B9") (pinfunction "GND_B9") (pintype "bidirectional"))
      (node (ref "U5") (pin "C13") (pinfunction "GND_C13") (pintype "bidirectional"))
      (node (ref "U5") (pin "C2") (pinfunction "GND_C2") (pintype "bidirectional"))
      (node (ref "U5") (pin "C6") (pinfunction "GND_C6") (pintype "bidirectional"))
      (node (ref "U5") (pin "C7") (pinfunction "GND_C7") (pintype "bidirectional"))
      (node (ref "U5") (pin "C8") (pinfunction "GND_C8") (pintype "bidirectional"))
      (node (ref "U5") (pin "C9") (pinfunction "GND_C9") (pintype "bidirectional"))
      (node (ref "U5") (pin "D11") (pinfunction "GND_D11") (pintype "bidirectional"))
      (node (ref "U5") (pin "D5") (pinfunction "GND_D5") (pintype "bidirectional"))
      (node (ref "U5") (pin "D7") (pinfunction "GND_D7") (pintype "bidirectional"))
      (node (ref "U5") (pin "D9") (pinfunction "GND_D9") (pintype "bidirectional"))
      (node (ref "U5") (pin "E1") (pinfunction "GND_E1") (pintype "bidirectional"))
      (node (ref "U5") (pin "E10") (pinfunction "GND_E10") (pintype "bidirectional"))
      (node (ref "U5") (pin "E14") (pinfunction "GND_E14") (pintype "bidirectional"))
      (node (ref "U5") (pin "E3") (pinfunction "GND_E3") (pintype "bidirectional"))
      (node (ref "U5") (pin "E6") (pinfunction "GND_E6") (pintype "bidirectional"))
      (node (ref "U5") (pin "E8") (pinfunction "GND_E8") (pintype "bidirectional"))
      (node (ref "U5") (pin "F5") (pinfunction "GND_F5") (pintype "bidirectional"))
      (node (ref "U5") (pin "F9") (pinfunction "GND_F9") (pintype "bidirectional"))
      (node (ref "U5") (pin "G10") (pinfunction "GND_G10") (pintype "bidirectional"))
      (node (ref "U5") (pin "G12") (pinfunction "GND_G12") (pintype "bidirectional"))
      (node (ref "U5") (pin "G3") (pinfunction "GND_G3") (pintype "bidirectional"))
      (node (ref "U5") (pin "G6") (pinfunction "GND_G6") (pintype "bidirectional"))
      (node (ref "U5") (pin "H5") (pinfunction "GND_H5") (pintype "bidirectional"))
      (node (ref "U5") (pin "H9") (pinfunction "GND_H9") (pintype "bidirectional"))
      (node (ref "U5") (pin "J10") (pinfunction "GND_J10") (pintype "bidirectional"))
      (node (ref "U5") (pin "J6") (pinfunction "GND_J6") (pintype "bidirectional"))
      (node (ref "U5") (pin "J7") (pinfunction "DXN_0_J7") (pintype "bidirectional"))
      (node (ref "U5") (pin "J8") (pinfunction "DXP_0_J8") (pintype "bidirectional"))
      (node (ref "U5") (pin "K1") (pinfunction "GND_K1") (pintype "bidirectional"))
      (node (ref "U5") (pin "K14") (pinfunction "GND_K14") (pintype "bidirectional"))
      (node (ref "U5") (pin "K5") (pinfunction "GND_K5") (pintype "bidirectional"))
      (node (ref "U5") (pin "K7") (pinfunction "GND_K7") (pintype "bidirectional"))
      (node (ref "U5") (pin "K9") (pinfunction "GND_K9") (pintype "bidirectional"))
      (node (ref "U5") (pin "L10") (pinfunction "GND_L10") (pintype "bidirectional"))
      (node (ref "U5") (pin "L11") (pinfunction "GND_L11") (pintype "bidirectional"))
      (node (ref "U5") (pin "L12") (pinfunction "IO_L16P_T2_CSI_B_14_L12") (pintype "bidirectional"))
      (node (ref "U5") (pin "L4") (pinfunction "GND_L4") (pintype "bidirectional"))
      (node (ref "U5") (pin "L6") (pinfunction "GND_L6") (pintype "bidirectional"))
      (node (ref "U5") (pin "L8") (pinfunction "GND_L8") (pintype "bidirectional"))
      (node (ref "U5") (pin "M13") (pinfunction "IO_L15P_T2_DQS_RDWR_B_14_M13") (pintype "bidirectional"))
      (node (ref "U5") (pin "N12") (pinfunction "GND_N12") (pintype "bidirectional"))
      (node (ref "U5") (pin "N3") (pinfunction "GND_N3") (pintype "bidirectional"))
      (node (ref "U5") (pin "N5") (pinfunction "GND_N5") (pintype "bidirectional"))
      (node (ref "U5") (pin "N9") (pinfunction "GND_N9") (pintype "bidirectional"))
      (node (ref "U5") (pin "P1") (pinfunction "GND_P1") (pintype "bidirectional"))
      (node (ref "U5") (pin "P14") (pinfunction "GND_P14") (pintype "bidirectional"))
      (node (ref "U6") (pin "4") (pinfunction "VSS_4") (pintype "bidirectional"))
      (node (ref "U7") (pin "5") (pinfunction "GND_5") (pintype "bidirectional"))
      (node (ref "U7") (pin "P$1") (pinfunction "GND_P$1") (pintype "bidirectional"))
      (node (ref "U7") (pin "P$2") (pinfunction "GND_P$2") (pintype "bidirectional"))
      (node (ref "U7") (pin "P$3") (pinfunction "GND_P$3") (pintype "bidirectional"))
      (node (ref "U7") (pin "P$4") (pinfunction "GND_P$4") (pintype "bidirectional"))
      (node (ref "U8") (pin "5") (pinfunction "GND_5") (pintype "bidirectional"))
      (node (ref "U8") (pin "P$1") (pinfunction "GND_P$1") (pintype "bidirectional"))
      (node (ref "U8") (pin "P$2") (pinfunction "GND_P$2") (pintype "bidirectional"))
      (node (ref "U8") (pin "P$3") (pinfunction "GND_P$3") (pintype "bidirectional"))
      (node (ref "U8") (pin "P$4") (pinfunction "GND_P$4") (pintype "bidirectional"))
      (node (ref "U9") (pin "5") (pinfunction "GND_5") (pintype "bidirectional"))
      (node (ref "U9") (pin "P$1") (pinfunction "GND_P$1") (pintype "bidirectional"))
      (node (ref "U9") (pin "P$2") (pinfunction "GND_P$2") (pintype "bidirectional"))
      (node (ref "U9") (pin "P$3") (pinfunction "GND_P$3") (pintype "bidirectional"))
      (node (ref "U9") (pin "P$4") (pinfunction "GND_P$4") (pintype "bidirectional"))
      (node (ref "X3") (pin "2") (pinfunction "GND_2") (pintype "bidirectional"))
      (node (ref "X4") (pin "2") (pinfunction "GND_2") (pintype "bidirectional"))
      (node (ref "X5") (pin "2") (pinfunction "GND_2") (pintype "bidirectional"))
    )
    (net (code "52") (name "INIT_B") (class "Default")
      (node (ref "R21") (pin "1") (pinfunction "1_1") (pintype "bidirectional"))
      (node (ref "U1") (pin "58") (pinfunction "PF3(ADC3)_58") (pintype "bidirectional"))
      (node (ref "U5") (pin "P8") (pinfunction "INIT_B_0_P8") (pintype "bidirectional"))
    )
    (net (code "53") (name "JTAG_TCK") (class "Default")
      (node (ref "J9") (pin "3") (pinfunction "TCK_3") (pintype "bidirectional"))
      (node (ref "U1") (pin "57") (pinfunction "PF4(ADC4/TCK)_57") (pintype "bidirectional"))
      (node (ref "U5") (pin "A7") (pinfunction "TCK_0_A7") (pintype "bidirectional"))
    )
    (net (code "54") (name "JTAG_TDI") (class "Default")
      (node (ref "J9") (pin "5") (pinfunction "TDI_5") (pintype "bidirectional"))
      (node (ref "U1") (pin "54") (pinfunction "PF7(ADC7/TDI)_54") (pintype "bidirectional"))
      (node (ref "U5") (pin "P7") (pinfunction "TDI_0_P7") (pintype "bidirectional"))
    )
    (net (code "55") (name "JTAG_TDO") (class "Default")
      (node (ref "J9") (pin "4") (pinfunction "TDO_4") (pintype "bidirectional"))
      (node (ref "U1") (pin "55") (pinfunction "PF6(ADC6/TDO)_55") (pintype "bidirectional"))
      (node (ref "U5") (pin "P6") (pinfunction "TDO_0_P6") (pintype "bidirectional"))
    )
    (net (code "56") (name "JTAG_TMS") (class "Default")
      (node (ref "J9") (pin "6") (pinfunction "TMS_6") (pintype "bidirectional"))
      (node (ref "U1") (pin "56") (pinfunction "PF5(ADC5/TMS)_56") (pintype "bidirectional"))
      (node (ref "U5") (pin "M6") (pinfunction "TMS_0_M6") (pintype "bidirectional"))
    )
    (net (code "57") (name "MCU_LED0") (class "Default")
      (node (ref "R1") (pin "1") (pinfunction "1_1") (pintype "bidirectional"))
      (node (ref "U1") (pin "32") (pinfunction "(T0)PD7_32") (pintype "bidirectional"))
    )
    (net (code "58") (name "MCU_LED1") (class "Default")
      (node (ref "R2") (pin "1") (pinfunction "1_1") (pintype "bidirectional"))
      (node (ref "U1") (pin "31") (pinfunction "(T1)PD6_31") (pintype "bidirectional"))
    )
    (net (code "59") (name "MCU_LED2") (class "Default")
      (node (ref "R3") (pin "1") (pinfunction "1_1") (pintype "bidirectional"))
      (node (ref "U1") (pin "30") (pinfunction "(XCK1)PD5_30") (pintype "bidirectional"))
    )
    (net (code "60") (name "MCU_LED3") (class "Default")
      (node (ref "R4") (pin "1") (pinfunction "1_1") (pintype "bidirectional"))
      (node (ref "U1") (pin "29") (pinfunction "(ICP1)PD4_29") (pintype "bidirectional"))
    )
    (net (code "61") (name "MCU_RESET") (class "Default")
      (node (ref "J3") (pin "5") (pinfunction "RST_5") (pintype "bidirectional"))
      (node (ref "R8") (pin "1") (pinfunction "1_1") (pintype "bidirectional"))
      (node (ref "S1") (pin "2") (pinfunction "3_2") (pintype "bidirectional"))
      (node (ref "U1") (pin "20") (pinfunction "_RESET_20") (pintype "bidirectional"))
    )
    (net (code "62") (name "MCU_RX") (class "Default")
      (node (ref "J4") (pin "3") (pinfunction "2_3") (pintype "bidirectional"))
      (node (ref "U1") (pin "27") (pinfunction "(RXD1/INT2)PD2_27") (pintype "bidirectional"))
    )
    (net (code "63") (name "MCU_TX") (class "Default")
      (node (ref "J4") (pin "1") (pinfunction "1_1") (pintype "bidirectional"))
      (node (ref "U1") (pin "28") (pinfunction "(TXD1/INT3)PD3_28") (pintype "bidirectional"))
    )
    (net (code "64") (name "MCU_VCC") (class "Default")
      (node (ref "C1") (pin "1") (pinfunction "P$1_1") (pintype "bidirectional"))
      (node (ref "R34") (pin "1") (pinfunction "1_1") (pintype "bidirectional"))
      (node (ref "R7") (pin "1") (pinfunction "1_1") (pintype "bidirectional"))
      (node (ref "R8") (pin "2") (pinfunction "2_2") (pintype "bidirectional"))
      (node (ref "R9") (pin "1") (pinfunction "1_1") (pintype "bidirectional"))
      (node (ref "U1") (pin "21") (pinfunction "UVCC_21") (pintype "bidirectional"))
      (node (ref "U1") (pin "3") (pinfunction "UVCC_3") (pintype "bidirectional"))
      (node (ref "U1") (pin "52") (pinfunction "VCC_52") (pintype "bidirectional"))
      (node (ref "U1") (pin "62") (pinfunction "AREF_62") (pintype "bidirectional"))
      (node (ref "U1") (pin "64") (pinfunction "AVCC_64") (pintype "bidirectional"))
      (node (ref "U1") (pin "7") (pinfunction "UCAP_7") (pintype "bidirectional"))
      (node (ref "U8") (pin "4") (pinfunction "SENSE2-_4") (pintype "bidirectional"))
    )
    (net (code "65") (name "MODE0") (class "Default")
      (node (ref "R24") (pin "2") (pinfunction "2_2") (pintype "bidirectional"))
      (node (ref "S2") (pin "1") (pinfunction "1X_1") (pintype "bidirectional"))
      (node (ref "U5") (pin "M7") (pinfunction "M0_0_M7") (pintype "bidirectional"))
    )
    (net (code "66") (name "MODE1") (class "Default")
      (node (ref "R25") (pin "2") (pinfunction "2_2") (pintype "bidirectional"))
      (node (ref "S2") (pin "2") (pinfunction "2X_2") (pintype "bidirectional"))
      (node (ref "U5") (pin "M8") (pinfunction "M1_0_M8") (pintype "bidirectional"))
    )
    (net (code "67") (name "MODE2") (class "Default")
      (node (ref "R26") (pin "2") (pinfunction "2_2") (pintype "bidirectional"))
      (node (ref "S2") (pin "3") (pinfunction "3X_3") (pintype "bidirectional"))
      (node (ref "U5") (pin "M9") (pinfunction "M2_0_M9") (pintype "bidirectional"))
    )
    (net (code "68") (name "MONITORING") (class "Default")
      (node (ref "R16") (pin "2") (pinfunction "2_2") (pintype "bidirectional"))
      (node (ref "S2") (pin "4") (pinfunction "4X_4") (pintype "bidirectional"))
      (node (ref "U3") (pin "1") (pinfunction "PE6(INT6/AIN0)_1") (pintype "bidirectional"))
    )
    (net (code "69") (name "MON_HWB") (class "Default")
      (node (ref "J7") (pin "1") (pinfunction "1_1") (pintype "bidirectional"))
      (node (ref "R12") (pin "2") (pinfunction "2_2") (pintype "bidirectional"))
      (node (ref "U3") (pin "33") (pinfunction "PE2(HWB)_33") (pintype "bidirectional"))
    )
    (net (code "70") (name "MON_LED0") (class "Default")
      (node (ref "R10") (pin "1") (pinfunction "1_1") (pintype "bidirectional"))
      (node (ref "U3") (pin "20") (pinfunction "PD2(RXD1/INT2)_20") (pintype "bidirectional"))
    )
    (net (code "71") (name "MON_LED1") (class "Default")
      (node (ref "R11") (pin "1") (pinfunction "1_1") (pintype "bidirectional"))
      (node (ref "U3") (pin "21") (pinfunction "PD3(TXD1/INT3)_21") (pintype "bidirectional"))
    )
    (net (code "72") (name "MON_MISO") (class "Default")
      (node (ref "J6") (pin "1") (pinfunction "MISO_1") (pintype "bidirectional"))
      (node (ref "U3") (pin "11") (pinfunction "PB3(PDO/PCINT3/MISO)_11") (pintype "bidirectional"))
    )
    (net (code "73") (name "MON_MOSI") (class "Default")
      (node (ref "J6") (pin "4") (pinfunction "MOSI_4") (pintype "bidirectional"))
      (node (ref "U3") (pin "10") (pinfunction "PB2(PDI/PCINT2/MOSI)_10") (pintype "bidirectional"))
    )
    (net (code "74") (name "MON_RESET") (class "Default")
      (node (ref "J6") (pin "5") (pinfunction "RST_5") (pintype "bidirectional"))
      (node (ref "R17") (pin "2") (pinfunction "2_2") (pintype "bidirectional"))
      (node (ref "U3") (pin "13") (pinfunction "_RESET_13") (pintype "bidirectional"))
    )
    (net (code "75") (name "MON_SCK") (class "Default")
      (node (ref "J6") (pin "3") (pinfunction "SCK_3") (pintype "bidirectional"))
      (node (ref "U3") (pin "9") (pinfunction "PB1(PCINT1/SCL)_9") (pintype "bidirectional"))
    )
    (net (code "76") (name "MON_USB_D+") (class "Default")
      (node (ref "R15") (pin "1") (pinfunction "1_1") (pintype "bidirectional"))
      (node (ref "U3") (pin "4") (pinfunction "D+_4") (pintype "bidirectional"))
    )
    (net (code "77") (name "MON_USB_D-") (class "Default")
      (node (ref "R14") (pin "1") (pinfunction "1_1") (pintype "bidirectional"))
      (node (ref "U3") (pin "3") (pinfunction "D-_3") (pintype "bidirectional"))
    )
    (net (code "78") (name "MON_USB_VCC") (class "Default")
      (node (ref "J8") (pin "1") (pinfunction "VCC_1") (pintype "bidirectional"))
      (node (ref "U3") (pin "7") (pinfunction "VBUS_7") (pintype "bidirectional"))
    )
    (net (code "79") (name "Net-(C2-P$1)") (class "Default")
      (node (ref "C2") (pin "1") (pinfunction "P$1_1") (pintype "bidirectional"))
      (node (ref "U1") (pin "23") (pinfunction "XTAL2_23") (pintype "bidirectional"))
      (node (ref "X1") (pin "1") (pinfunction "P$1_1") (pintype "bidirectional"))
    )
    (net (code "80") (name "Net-(C3-P$1)") (class "Default")
      (node (ref "C3") (pin "1") (pinfunction "P$1_1") (pintype "bidirectional"))
      (node (ref "U1") (pin "24") (pinfunction "XTAL1_24") (pintype "bidirectional"))
      (node (ref "X1") (pin "3") (pinfunction "P$2_3") (pintype "bidirectional"))
    )
    (net (code "81") (name "Net-(C5-P$1)") (class "Default")
      (node (ref "C5") (pin "1") (pinfunction "P$1_1") (pintype "bidirectional"))
      (node (ref "U3") (pin "17") (pinfunction "XTAL1_17") (pintype "bidirectional"))
      (node (ref "X2") (pin "3") (pinfunction "P$2_3") (pintype "bidirectional"))
    )
    (net (code "82") (name "Net-(C6-P$1)") (class "Default")
      (node (ref "C6") (pin "1") (pinfunction "P$1_1") (pintype "bidirectional"))
      (node (ref "U3") (pin "16") (pinfunction "XTAL2_16") (pintype "bidirectional"))
      (node (ref "X2") (pin "1") (pinfunction "P$1_1") (pintype "bidirectional"))
    )
    (net (code "83") (name "Net-(D1-Pad1)") (class "Default")
      (node (ref "D1") (pin "1") (pinfunction "1_1") (pintype "bidirectional"))
      (node (ref "R1") (pin "2") (pinfunction "2_2") (pintype "bidirectional"))
    )
    (net (code "84") (name "Net-(D2-Pad1)") (class "Default")
      (node (ref "D2") (pin "1") (pinfunction "1_1") (pintype "bidirectional"))
      (node (ref "R2") (pin "2") (pinfunction "2_2") (pintype "bidirectional"))
    )
    (net (code "85") (name "Net-(D3-Pad1)") (class "Default")
      (node (ref "D3") (pin "1") (pinfunction "1_1") (pintype "bidirectional"))
      (node (ref "R3") (pin "2") (pinfunction "2_2") (pintype "bidirectional"))
    )
    (net (code "86") (name "Net-(D4-Pad1)") (class "Default")
      (node (ref "D4") (pin "1") (pinfunction "1_1") (pintype "bidirectional"))
      (node (ref "R4") (pin "2") (pinfunction "2_2") (pintype "bidirectional"))
    )
    (net (code "87") (name "Net-(D5-Pad1)") (class "Default")
      (node (ref "D5") (pin "1") (pinfunction "1_1") (pintype "bidirectional"))
      (node (ref "R10") (pin "2") (pinfunction "2_2") (pintype "bidirectional"))
    )
    (net (code "88") (name "Net-(D6-Pad1)") (class "Default")
      (node (ref "D6") (pin "1") (pinfunction "1_1") (pintype "bidirectional"))
      (node (ref "R11") (pin "2") (pinfunction "2_2") (pintype "bidirectional"))
    )
    (net (code "89") (name "Net-(D7-Pad1)") (class "Default")
      (node (ref "D7") (pin "1") (pinfunction "1_1") (pintype "bidirectional"))
      (node (ref "R18") (pin "2") (pinfunction "2_2") (pintype "bidirectional"))
    )
    (net (code "90") (name "Net-(D8-Pad1)") (class "Default")
      (node (ref "D8") (pin "1") (pinfunction "1_1") (pintype "bidirectional"))
      (node (ref "R19") (pin "2") (pinfunction "2_2") (pintype "bidirectional"))
    )
    (net (code "91") (name "Net-(D9-Pad1)") (class "Default")
      (node (ref "D9") (pin "1") (pinfunction "1_1") (pintype "bidirectional"))
      (node (ref "R20") (pin "2") (pinfunction "2_2") (pintype "bidirectional"))
    )
    (net (code "92") (name "Net-(D10-Pad1)") (class "Default")
      (node (ref "D10") (pin "1") (pinfunction "1_1") (pintype "bidirectional"))
      (node (ref "R22") (pin "2") (pinfunction "2_2") (pintype "bidirectional"))
    )
    (net (code "93") (name "Net-(D11-Pad2)") (class "Default")
      (node (ref "D11") (pin "2") (pinfunction "2_2") (pintype "bidirectional"))
      (node (ref "R49") (pin "2") (pinfunction "2_2") (pintype "bidirectional"))
    )
    (net (code "94") (name "Net-(J8-D+)") (class "Default")
      (node (ref "J8") (pin "3") (pinfunction "D+_3") (pintype "bidirectional"))
      (node (ref "R15") (pin "2") (pinfunction "2_2") (pintype "bidirectional"))
    )
    (net (code "95") (name "Net-(J8-D-)") (class "Default")
      (node (ref "J8") (pin "2") (pinfunction "D-_2") (pintype "bidirectional"))
      (node (ref "R14") (pin "2") (pinfunction "2_2") (pintype "bidirectional"))
    )
    (net (code "96") (name "Net-(L1-P$2)") (class "Default")
      (node (ref "L1") (pin "2") (pinfunction "P$2_2") (pintype "bidirectional"))
      (node (ref "U11") (pin "4") (pinfunction "SW1_4") (pintype "bidirectional"))
    )
    (net (code "97") (name "Net-(L2-P$1)") (class "Default")
      (node (ref "L2") (pin "1") (pinfunction "P$1_1") (pintype "bidirectional"))
      (node (ref "U12") (pin "4") (pinfunction "SW1_4") (pintype "bidirectional"))
    )
    (net (code "98") (name "Net-(L3-P$2)") (class "Default")
      (node (ref "L3") (pin "2") (pinfunction "P$2_2") (pintype "bidirectional"))
      (node (ref "U12") (pin "6") (pinfunction "SW2_6") (pintype "bidirectional"))
    )
    (net (code "99") (name "Net-(U1-D+)") (class "Default")
      (node (ref "R6") (pin "2") (pinfunction "2_2") (pintype "bidirectional"))
      (node (ref "U1") (pin "5") (pinfunction "D+_5") (pintype "bidirectional"))
    )
    (net (code "100") (name "Net-(U1-D-)") (class "Default")
      (node (ref "R5") (pin "2") (pinfunction "2_2") (pintype "bidirectional"))
      (node (ref "U1") (pin "4") (pinfunction "D-_4") (pintype "bidirectional"))
    )
    (net (code "101") (name "Net-(U3-UVCC)") (class "Default")
      (node (ref "R13") (pin "1") (pinfunction "1_1") (pintype "bidirectional"))
      (node (ref "U3") (pin "2") (pinfunction "UVCC_2") (pintype "bidirectional"))
    )
    (net (code "102") (name "Net-(U7-ADDR_SEL)") (class "Default")
      (node (ref "R35") (pin "2") (pinfunction "2_2") (pintype "bidirectional"))
      (node (ref "U7") (pin "6") (pinfunction "ADDR_SEL_6") (pintype "bidirectional"))
    )
    (net (code "103") (name "Net-(U8-ADDR_SEL)") (class "Default")
      (node (ref "R36") (pin "2") (pinfunction "2_2") (pintype "bidirectional"))
      (node (ref "U8") (pin "6") (pinfunction "ADDR_SEL_6") (pintype "bidirectional"))
    )
    (net (code "104") (name "Net-(U9-ADDR_SEL)") (class "Default")
      (node (ref "R41") (pin "2") (pinfunction "2_2") (pintype "bidirectional"))
      (node (ref "U9") (pin "6") (pinfunction "ADDR_SEL_6") (pintype "bidirectional"))
    )
    (net (code "105") (name "Net-(U10-ADDR_SEL)") (class "Default")
      (node (ref "R42") (pin "2") (pinfunction "2_2") (pintype "bidirectional"))
      (node (ref "U10") (pin "6") (pinfunction "ADDR_SEL_6") (pintype "bidirectional"))
    )
    (net (code "106") (name "Net-(U11-VFB1)") (class "Default")
      (node (ref "R43") (pin "1") (pinfunction "1_1") (pintype "bidirectional"))
      (node (ref "R46") (pin "1") (pinfunction "1_1") (pintype "bidirectional"))
      (node (ref "U11") (pin "1") (pinfunction "VFB1_1") (pintype "bidirectional"))
    )
    (net (code "107") (name "Net-(U12-VFB1)") (class "Default")
      (node (ref "R44") (pin "1") (pinfunction "1_1") (pintype "bidirectional"))
      (node (ref "R47") (pin "1") (pinfunction "1_1") (pintype "bidirectional"))
      (node (ref "U12") (pin "1") (pinfunction "VFB1_1") (pintype "bidirectional"))
    )
    (net (code "108") (name "Net-(U12-VFB2)") (class "Default")
      (node (ref "R45") (pin "2") (pinfunction "2_2") (pintype "bidirectional"))
      (node (ref "R48") (pin "2") (pinfunction "2_2") (pintype "bidirectional"))
      (node (ref "U12") (pin "8") (pinfunction "VFB2_8") (pintype "bidirectional"))
    )
    (net (code "109") (name "OSC_32") (class "Default")
      (node (ref "U5") (pin "H11") (pinfunction "IO_L13P_T2_MRCC_14_H11") (pintype "bidirectional"))
      (node (ref "X5") (pin "3") (pinfunction "OUTPUT_3") (pintype "bidirectional"))
    )
    (net (code "110") (name "OSC_50") (class "Default")
      (node (ref "U5") (pin "F11") (pinfunction "IO_L12N_T1_MRCC_14_F11") (pintype "bidirectional"))
      (node (ref "X4") (pin "3") (pinfunction "OUTPUT_3") (pintype "bidirectional"))
    )
    (net (code "111") (name "OSC_100") (class "Default")
      (node (ref "U5") (pin "A10") (pinfunction "IO_L3N_T0_DQS_EMCCLK_14_A10") (pintype "bidirectional"))
      (node (ref "X3") (pin "3") (pinfunction "OUTPUT_3") (pintype "bidirectional"))
    )
    (net (code "112") (name "SCL") (class "Default")
      (node (ref "J1") (pin "1") (pinfunction "1_1") (pintype "bidirectional"))
      (node (ref "R29") (pin "1") (pinfunction "1_1") (pintype "bidirectional"))
      (node (ref "U1") (pin "25") (pinfunction "(OC0B/SCL/INT0)PD0_25") (pintype "bidirectional"))
      (node (ref "U10") (pin "9") (pinfunction "SMCLK_9") (pintype "bidirectional"))
      (node (ref "U3") (pin "18") (pinfunction "PD0(OC0B/SCL/INT0)_18") (pintype "bidirectional"))
      (node (ref "U7") (pin "9") (pinfunction "SMCLK_9") (pintype "bidirectional"))
      (node (ref "U8") (pin "9") (pinfunction "SMCLK_9") (pintype "bidirectional"))
      (node (ref "U9") (pin "9") (pinfunction "SMCLK_9") (pintype "bidirectional"))
    )
    (net (code "113") (name "SDA") (class "Default")
      (node (ref "J1") (pin "2") (pinfunction "2_2") (pintype "bidirectional"))
      (node (ref "R30") (pin "1") (pinfunction "1_1") (pintype "bidirectional"))
      (node (ref "U1") (pin "26") (pinfunction "(OC2B/SDA/INT1)PD1_26") (pintype "bidirectional"))
      (node (ref "U10") (pin "8") (pinfunction "SMDATA_8") (pintype "bidirectional"))
      (node (ref "U3") (pin "19") (pinfunction "PD1(SDA/INT1)_19") (pintype "bidirectional"))
      (node (ref "U7") (pin "8") (pinfunction "SMDATA_8") (pintype "bidirectional"))
      (node (ref "U8") (pin "8") (pinfunction "SMDATA_8") (pintype "bidirectional"))
      (node (ref "U9") (pin "8") (pinfunction "SMDATA_8") (pintype "bidirectional"))
    )
    (net (code "114") (name "SPI_CS") (class "Default")
      (node (ref "R27") (pin "2") (pinfunction "2_2") (pintype "bidirectional"))
      (node (ref "U1") (pin "14") (pinfunction "(PCINT4/OC.2A)PB4_14") (pintype "bidirectional"))
      (node (ref "U5") (pin "C11") (pinfunction "IO_L6P_T0_FCS_B_14_C11") (pintype "bidirectional"))
      (node (ref "U6") (pin "1") (pinfunction "CE_1") (pintype "bidirectional"))
    )
    (net (code "115") (name "SPI_SCK{slash}CCLK") (class "Default")
      (node (ref "J3") (pin "3") (pinfunction "SCK_3") (pintype "bidirectional"))
      (node (ref "U1") (pin "11") (pinfunction "(PCINT1/SCLK)PB1_11") (pintype "bidirectional"))
      (node (ref "U2") (pin "6") (pinfunction "SCK_6") (pintype "bidirectional"))
      (node (ref "U5") (pin "A8") (pinfunction "CCLK_0_A8") (pintype "bidirectional"))
      (node (ref "U6") (pin "6") (pinfunction "SCK_6") (pintype "bidirectional"))
    )
    (net (code "116") (name "SRAM_A0") (class "Default")
      (node (ref "U4") (pin "5") (pinfunction "A0_5") (pintype "bidirectional"))
      (node (ref "U5") (pin "B3") (pinfunction "IO_L3P_T0_DQS_34_B3") (pintype "bidirectional"))
    )
    (net (code "117") (name "SRAM_A1") (class "Default")
      (node (ref "U4") (pin "4") (pinfunction "A1_4") (pintype "bidirectional"))
      (node (ref "U5") (pin "B2") (pinfunction "IO_L5P_T0_34_B2") (pintype "bidirectional"))
    )
    (net (code "118") (name "SRAM_A2") (class "Default")
      (node (ref "U4") (pin "3") (pinfunction "A2_3") (pintype "bidirectional"))
      (node (ref "U5") (pin "B5") (pinfunction "IO_L4P_T0_34_B5") (pintype "bidirectional"))
    )
    (net (code "119") (name "SRAM_A3") (class "Default")
      (node (ref "U4") (pin "2") (pinfunction "A3_2") (pintype "bidirectional"))
      (node (ref "U5") (pin "B6") (pinfunction "IO_0_34_B6") (pintype "bidirectional"))
    )
    (net (code "120") (name "SRAM_A4") (class "Default")
      (node (ref "U4") (pin "1") (pinfunction "A4_1") (pintype "bidirectional"))
      (node (ref "U5") (pin "A5") (pinfunction "IO_L4N_T0_34_A5") (pintype "bidirectional"))
    )
    (net (code "121") (name "SRAM_A5") (class "Default")
      (node (ref "U4") (pin "44") (pinfunction "A5_44") (pintype "bidirectional"))
      (node (ref "U5") (pin "A4") (pinfunction "IO_L2P_T0_34_A4") (pintype "bidirectional"))
    )
    (net (code "122") (name "SRAM_A6") (class "Default")
      (node (ref "U4") (pin "43") (pinfunction "A6_43") (pintype "bidirectional"))
      (node (ref "U5") (pin "A3") (pinfunction "IO_L2N_T0_34_A3") (pintype "bidirectional"))
    )
    (net (code "123") (name "SRAM_A7") (class "Default")
      (node (ref "U4") (pin "42") (pinfunction "A7_42") (pintype "bidirectional"))
      (node (ref "U5") (pin "A2") (pinfunction "IO_L3N_T0_DQS_34_A2") (pintype "bidirectional"))
    )
    (net (code "124") (name "SRAM_A8") (class "Default")
      (node (ref "U4") (pin "27") (pinfunction "A8_27") (pintype "bidirectional"))
      (node (ref "U5") (pin "M3") (pinfunction "IO_L19P_T3_34_M3") (pintype "bidirectional"))
    )
    (net (code "125") (name "SRAM_A9") (class "Default")
      (node (ref "U4") (pin "26") (pinfunction "A9_26") (pintype "bidirectional"))
      (node (ref "U5") (pin "M4") (pinfunction "IO_L23N_T3_34_M4") (pintype "bidirectional"))
    )
    (net (code "126") (name "SRAM_A10") (class "Default")
      (node (ref "U4") (pin "25") (pinfunction "A10_25") (pintype "bidirectional"))
      (node (ref "U5") (pin "M5") (pinfunction "IO_L23P_T3_34_M5") (pintype "bidirectional"))
    )
    (net (code "127") (name "SRAM_A11") (class "Default")
      (node (ref "U4") (pin "24") (pinfunction "A11_24") (pintype "bidirectional"))
      (node (ref "U5") (pin "N1") (pinfunction "IO_L20N_T3_34_N1") (pintype "bidirectional"))
    )
    (net (code "128") (name "SRAM_A12") (class "Default")
      (node (ref "U4") (pin "22") (pinfunction "A12_22") (pintype "bidirectional"))
      (node (ref "U5") (pin "P5") (pinfunction "IO_L24P_T3_34_P5") (pintype "bidirectional"))
    )
    (net (code "129") (name "SRAM_A13") (class "Default")
      (node (ref "U4") (pin "21") (pinfunction "A13_21") (pintype "bidirectional"))
      (node (ref "U5") (pin "P4") (pinfunction "IO_L21P_T3_DQS_34_P4") (pintype "bidirectional"))
    )
    (net (code "130") (name "SRAM_A14") (class "Default")
      (node (ref "U4") (pin "20") (pinfunction "A14_20") (pintype "bidirectional"))
      (node (ref "U5") (pin "P3") (pinfunction "IO_L21N_T3_DQS_34_P3") (pintype "bidirectional"))
    )
    (net (code "131") (name "SRAM_A15") (class "Default")
      (node (ref "U4") (pin "19") (pinfunction "A15_19") (pintype "bidirectional"))
      (node (ref "U5") (pin "P2") (pinfunction "IO_L20P_T3_34_P2") (pintype "bidirectional"))
    )
    (net (code "132") (name "SRAM_A16") (class "Default")
      (node (ref "U4") (pin "18") (pinfunction "A16_18") (pintype "bidirectional"))
      (node (ref "U5") (pin "J4") (pinfunction "IO_L17P_T2_34_J4") (pintype "bidirectional"))
    )
    (net (code "133") (name "SRAM_A17") (class "Default")
      (node (ref "U4") (pin "23") (pinfunction "A17_23") (pintype "bidirectional"))
      (node (ref "U5") (pin "N4") (pinfunction "IO_L24N_T3_34_N4") (pintype "bidirectional"))
    )
    (net (code "134") (name "SRAM_A18") (class "Default")
      (node (ref "U4") (pin "28") (pinfunction "A18_28") (pintype "bidirectional"))
      (node (ref "U5") (pin "M2") (pinfunction "IO_L19N_T3_VREF_34_M2") (pintype "bidirectional"))
    )
    (net (code "135") (name "SRAM_CS") (class "Default")
      (node (ref "U4") (pin "6") (pinfunction "CS1#_6") (pintype "bidirectional"))
      (node (ref "U5") (pin "C3") (pinfunction "IO_L1N_T0_34_C3") (pintype "bidirectional"))
    )
    (net (code "136") (name "SRAM_D0") (class "Default")
      (node (ref "U4") (pin "7") (pinfunction "I/O0_7") (pintype "bidirectional"))
      (node (ref "U5") (pin "C4") (pinfunction "IO_L6N_T0_VREF_34_C4") (pintype "bidirectional"))
    )
    (net (code "137") (name "SRAM_D1") (class "Default")
      (node (ref "U4") (pin "8") (pinfunction "I/O1_8") (pintype "bidirectional"))
      (node (ref "U5") (pin "D2") (pinfunction "IO_L10N_T1_34_D2") (pintype "bidirectional"))
    )
    (net (code "138") (name "SRAM_D2") (class "Default")
      (node (ref "U4") (pin "9") (pinfunction "I/O2_9") (pintype "bidirectional"))
      (node (ref "U5") (pin "D3") (pinfunction "IO_L1P_T0_34_D3") (pintype "bidirectional"))
    )
    (net (code "139") (name "SRAM_D3") (class "Default")
      (node (ref "U4") (pin "10") (pinfunction "I/O3_10") (pintype "bidirectional"))
      (node (ref "U5") (pin "E2") (pinfunction "IO_L10P_T1_34_E2") (pintype "bidirectional"))
    )
    (net (code "140") (name "SRAM_D4") (class "Default")
      (node (ref "U4") (pin "13") (pinfunction "I/O4_13") (pintype "bidirectional"))
      (node (ref "U5") (pin "F2") (pinfunction "IO_L8N_T1_34_F2") (pintype "bidirectional"))
    )
    (net (code "141") (name "SRAM_D5") (class "Default")
      (node (ref "U4") (pin "14") (pinfunction "I/O5_14") (pintype "bidirectional"))
      (node (ref "U5") (pin "F3") (pinfunction "IO_L8P_T1_34_F3") (pintype "bidirectional"))
    )
    (net (code "142") (name "SRAM_D6") (class "Default")
      (node (ref "U4") (pin "15") (pinfunction "I/O6_15") (pintype "bidirectional"))
      (node (ref "U5") (pin "H2") (pinfunction "IO_L14P_T2_SRCC_34_H2") (pintype "bidirectional"))
    )
    (net (code "143") (name "SRAM_D7") (class "Default")
      (node (ref "U4") (pin "16") (pinfunction "I/O7_16") (pintype "bidirectional"))
      (node (ref "U5") (pin "H3") (pinfunction "IO_L13N_T2_MRCC_34_H3") (pintype "bidirectional"))
    )
    (net (code "144") (name "SRAM_D8") (class "Default")
      (node (ref "U4") (pin "29") (pinfunction "I/O8_29") (pintype "bidirectional"))
      (node (ref "U5") (pin "M1") (pinfunction "IO_L18P_T2_34_M1") (pintype "bidirectional"))
    )
    (net (code "145") (name "SRAM_D9") (class "Default")
      (node (ref "U4") (pin "30") (pinfunction "I/O9_30") (pintype "bidirectional"))
      (node (ref "U5") (pin "L3") (pinfunction "IO_L22P_T3_34_L3") (pintype "bidirectional"))
    )
    (net (code "146") (name "SRAM_D10") (class "Default")
      (node (ref "U4") (pin "31") (pinfunction "I/O10_31") (pintype "bidirectional"))
      (node (ref "U5") (pin "L1") (pinfunction "IO_L18N_T2_34_L1") (pintype "bidirectional"))
    )
    (net (code "147") (name "SRAM_D11") (class "Default")
      (node (ref "U4") (pin "32") (pinfunction "I/O11_32") (pintype "bidirectional"))
      (node (ref "U5") (pin "L2") (pinfunction "IO_L22N_T3_34_L2") (pintype "bidirectional"))
    )
    (net (code "148") (name "SRAM_D12") (class "Default")
      (node (ref "U4") (pin "35") (pinfunction "I/O12_35") (pintype "bidirectional"))
      (node (ref "U5") (pin "J1") (pinfunction "IO_L15N_T2_DQS_34_J1") (pintype "bidirectional"))
    )
    (net (code "149") (name "SRAM_D13") (class "Default")
      (node (ref "U4") (pin "36") (pinfunction "I/O13_36") (pintype "bidirectional"))
      (node (ref "U5") (pin "H1") (pinfunction "IO_L14N_T2_SRCC_34_H1") (pintype "bidirectional"))
    )
    (net (code "150") (name "SRAM_D14") (class "Default")
      (node (ref "U4") (pin "37") (pinfunction "I/O14_37") (pintype "bidirectional"))
      (node (ref "U5") (pin "G1") (pinfunction "IO_L9P_T1_DQS_34_G1") (pintype "bidirectional"))
    )
    (net (code "151") (name "SRAM_D15") (class "Default")
      (node (ref "U4") (pin "38") (pinfunction "I/O15_38") (pintype "bidirectional"))
      (node (ref "U5") (pin "F1") (pinfunction "IO_L9N_T1_DQS_34_F1") (pintype "bidirectional"))
    )
    (net (code "152") (name "SRAM_LB") (class "Default")
      (node (ref "U4") (pin "39") (pinfunction "LB#_39") (pintype "bidirectional"))
      (node (ref "U5") (pin "D1") (pinfunction "IO_L11P_T1_SRCC_34_D1") (pintype "bidirectional"))
    )
    (net (code "153") (name "SRAM_OE") (class "Default")
      (node (ref "U4") (pin "41") (pinfunction "OE#_41") (pintype "bidirectional"))
      (node (ref "U5") (pin "B1") (pinfunction "IO_L5N_T0_34_B1") (pintype "bidirectional"))
    )
    (net (code "154") (name "SRAM_POWER") (class "Default")
      (node (ref "M4") (pin "4") (pinfunction "G_4") (pintype "bidirectional"))
      (node (ref "U1") (pin "19") (pinfunction "(INT.5/TOSC2)PE5_19") (pintype "bidirectional"))
    )
    (net (code "155") (name "SRAM_UB") (class "Default")
      (node (ref "U4") (pin "40") (pinfunction "UB#_40") (pintype "bidirectional"))
      (node (ref "U5") (pin "C1") (pinfunction "IO_L11N_T1_SRCC_34_C1") (pintype "bidirectional"))
    )
    (net (code "156") (name "SRAM_VDD") (class "Default")
      (node (ref "C24") (pin "1") (pinfunction "P$1_1") (pintype "bidirectional"))
      (node (ref "C25") (pin "1") (pinfunction "P$1_1") (pintype "bidirectional"))
      (node (ref "C26") (pin "1") (pinfunction "P$1_1") (pintype "bidirectional"))
      (node (ref "C27") (pin "1") (pinfunction "P$1_1") (pintype "bidirectional"))
      (node (ref "C28") (pin "1") (pinfunction "P$1_1") (pintype "bidirectional"))
      (node (ref "C29") (pin "1") (pinfunction "P$1_1") (pintype "bidirectional"))
      (node (ref "C30") (pin "1") (pinfunction "P$1_1") (pintype "bidirectional"))
      (node (ref "M4") (pin "5") (pinfunction "D_5") (pintype "bidirectional"))
      (node (ref "M4") (pin "6") (pinfunction "D_6") (pintype "bidirectional"))
      (node (ref "M4") (pin "7") (pinfunction "D_7") (pintype "bidirectional"))
      (node (ref "M4") (pin "8") (pinfunction "D_8") (pintype "bidirectional"))
      (node (ref "U4") (pin "11") (pinfunction "VDD_11") (pintype "bidirectional"))
      (node (ref "U4") (pin "33") (pinfunction "VDD_33") (pintype "bidirectional"))
      (node (ref "U5") (pin "G2") (pinfunction "VCCO_34_G2") (pintype "bidirectional"))
      (node (ref "U5") (pin "K2") (pinfunction "VCCO_34_K2") (pintype "bidirectional"))
      (node (ref "U5") (pin "N2") (pinfunction "VCCO_34_N2") (pintype "bidirectional"))
    )
    (net (code "157") (name "SRAM_VDD_MON") (class "Default")
      (node (ref "M4") (pin "1") (pinfunction "S_1") (pintype "bidirectional"))
      (node (ref "M4") (pin "2") (pinfunction "S_2") (pintype "bidirectional"))
      (node (ref "M4") (pin "3") (pinfunction "S_3") (pintype "bidirectional"))
      (node (ref "R31") (pin "1") (pinfunction "1_1") (pintype "bidirectional"))
      (node (ref "U7") (pin "2") (pinfunction "SENSE1-_2") (pintype "bidirectional"))
    )
    (net (code "158") (name "SRAM_WE") (class "Default")
      (node (ref "U4") (pin "17") (pinfunction "WE#_17") (pintype "bidirectional"))
      (node (ref "U5") (pin "H4") (pinfunction "IO_L13P_T2_MRCC_34_H4") (pintype "bidirectional"))
    )
    (net (code "159") (name "UID") (class "Default")
      (node (ref "J11") (pin "4") (pinfunction "UID_4") (pintype "bidirectional"))
      (node (ref "U1") (pin "9") (pinfunction "(IUID)PE3_9") (pintype "bidirectional"))
    )
    (net (code "160") (name "USBD+") (class "Default")
      (node (ref "J11") (pin "3") (pinfunction "D+_3") (pintype "bidirectional"))
      (node (ref "R6") (pin "1") (pinfunction "1_1") (pintype "bidirectional"))
    )
    (net (code "161") (name "USBD-") (class "Default")
      (node (ref "J11") (pin "2") (pinfunction "D-_2") (pintype "bidirectional"))
      (node (ref "R5") (pin "1") (pinfunction "1_1") (pintype "bidirectional"))
    )
    (net (code "162") (name "USB_VCC_RAW") (class "Default")
      (node (ref "D11") (pin "1") (pinfunction "1_1") (pintype "bidirectional"))
      (node (ref "J11") (pin "1") (pinfunction "VCC_1") (pintype "bidirectional"))
      (node (ref "R39") (pin "1") (pinfunction "1_1") (pintype "bidirectional"))
      (node (ref "U1") (pin "8") (pinfunction "VBUS_8") (pintype "bidirectional"))
      (node (ref "U9") (pin "4") (pinfunction "SENSE2-_4") (pintype "bidirectional"))
    )
    (net (code "163") (name "WIRELESS_CS") (class "Default")
      (node (ref "R7") (pin "2") (pinfunction "2_2") (pintype "bidirectional"))
      (node (ref "U1") (pin "1") (pinfunction "(INT.6/AIN.0)PE6_1") (pintype "bidirectional"))
      (node (ref "U2") (pin "8") (pinfunction "_CS_8") (pintype "bidirectional"))
    )
    (net (code "164") (name "WIRELESS_INT") (class "Default")
      (node (ref "U1") (pin "61") (pinfunction "PF0(ADC0)_61") (pintype "bidirectional"))
      (node (ref "U2") (pin "4") (pinfunction "INT_4") (pintype "bidirectional"))
    )
    (net (code "165") (name "WIRELESS_RESET") (class "Default")
      (node (ref "U1") (pin "15") (pinfunction "(PCINT5/OC.1A)PB5_15") (pintype "bidirectional"))
      (node (ref "U2") (pin "2") (pinfunction "_RESET_2") (pintype "bidirectional"))
    )
    (net (code "166") (name "WIRELESS_VCC") (class "Default")
      (node (ref "R37") (pin "1") (pinfunction "1_1") (pintype "bidirectional"))
      (node (ref "U2") (pin "10") (pinfunction "VI_10") (pintype "bidirectional"))
      (node (ref "U9") (pin "2") (pinfunction "SENSE1-_2") (pintype "bidirectional"))
    )
    (net (code "167") (name "WIRELESS_WAKE") (class "Default")
      (node (ref "U1") (pin "60") (pinfunction "PF1(ADC1)_60") (pintype "bidirectional"))
      (node (ref "U2") (pin "3") (pinfunction "WAKE_3") (pintype "bidirectional"))
    )
    (net (code "168") (name "XMEM_A8") (class "Default")
      (node (ref "J1") (pin "10") (pinfunction "10_10") (pintype "bidirectional"))
      (node (ref "U1") (pin "35") (pinfunction "PC0(A8)_35") (pintype "bidirectional"))
      (node (ref "U5") (pin "D13") (pinfunction "IO_L8N_T1_D12_14_D13") (pintype "bidirectional"))
    )
    (net (code "169") (name "XMEM_A9") (class "Default")
      (node (ref "J1") (pin "9") (pinfunction "9_9") (pintype "bidirectional"))
      (node (ref "U1") (pin "36") (pinfunction "PC1(A9)_36") (pintype "bidirectional"))
      (node (ref "U5") (pin "D12") (pinfunction "IO_L8P_T1_D11_14_D12") (pintype "bidirectional"))
    )
    (net (code "170") (name "XMEM_A10") (class "Default")
      (node (ref "J2") (pin "6") (pinfunction "6_6") (pintype "bidirectional"))
      (node (ref "U1") (pin "37") (pinfunction "PC2(A10)_37") (pintype "bidirectional"))
      (node (ref "U5") (pin "E13") (pinfunction "IO_L10N_T1_D15_14_E13") (pintype "bidirectional"))
    )
    (net (code "171") (name "XMEM_A11") (class "Default")
      (node (ref "J2") (pin "5") (pinfunction "5_5") (pintype "bidirectional"))
      (node (ref "U1") (pin "38") (pinfunction "PC3(A11/T.3)_38") (pintype "bidirectional"))
      (node (ref "U5") (pin "E12") (pinfunction "IO_L7N_T1_D10_14_E12") (pintype "bidirectional"))
    )
    (net (code "172") (name "XMEM_A12") (class "Default")
      (node (ref "J2") (pin "4") (pinfunction "4_4") (pintype "bidirectional"))
      (node (ref "U1") (pin "39") (pinfunction "PC4(A12/OC.3C)_39") (pintype "bidirectional"))
      (node (ref "U5") (pin "F14") (pinfunction "IO_L9N_T1_DQS_D13_14_F14") (pintype "bidirectional"))
    )
    (net (code "173") (name "XMEM_A13") (class "Default")
      (node (ref "J2") (pin "3") (pinfunction "3_3") (pintype "bidirectional"))
      (node (ref "U1") (pin "40") (pinfunction "PC5(A13/OC.3B)_40") (pintype "bidirectional"))
      (node (ref "U5") (pin "F13") (pinfunction "IO_L10P_T1_D14_14_F13") (pintype "bidirectional"))
    )
    (net (code "174") (name "XMEM_A14") (class "Default")
      (node (ref "J2") (pin "2") (pinfunction "2_2") (pintype "bidirectional"))
      (node (ref "U1") (pin "41") (pinfunction "PC6(A14/OC.3A)_41") (pintype "bidirectional"))
      (node (ref "U5") (pin "F12") (pinfunction "IO_L7P_T1_D09_14_F12") (pintype "bidirectional"))
    )
    (net (code "175") (name "XMEM_A15") (class "Default")
      (node (ref "J2") (pin "1") (pinfunction "1_1") (pintype "bidirectional"))
      (node (ref "U1") (pin "42") (pinfunction "PC7(A15/IC.3/CLKO)_42") (pintype "bidirectional"))
      (node (ref "U5") (pin "G14") (pinfunction "IO_L9P_T1_DQS_14_G14") (pintype "bidirectional"))
    )
    (net (code "176") (name "XMEM_RD") (class "Default")
      (node (ref "U1") (pin "34") (pinfunction "PE1(_RD)_34") (pintype "bidirectional"))
      (node (ref "U5") (pin "D14") (pinfunction "IO_L11P_T1_SRCC_14_D14") (pintype "bidirectional"))
    )
    (net (code "177") (name "XMEM_WR") (class "Default")
      (node (ref "U1") (pin "33") (pinfunction "PE0(_WR)_33") (pintype "bidirectional"))
      (node (ref "U5") (pin "C14") (pinfunction "IO_L11N_T1_SRCC_14_C14") (pintype "bidirectional"))
    )
    (net (code "178") (name "unconnected-(J8-SHIELD-PadCASE_1)") (class "Default")
      (node (ref "J8") (pin "CASE_1") (pinfunction "SHIELD_CASE_1") (pintype "bidirectional"))
    )
    (net (code "179") (name "unconnected-(J8-UID-Pad4)") (class "Default")
      (node (ref "J8") (pin "4") (pinfunction "UID_4") (pintype "bidirectional"))
    )
    (net (code "180") (name "unconnected-(J11-SHIELD-PadCASE_1)") (class "Default")
      (node (ref "J11") (pin "CASE_1") (pinfunction "SHIELD_CASE_1") (pintype "bidirectional"))
    )
    (net (code "181") (name "unconnected-(U3-AREF-Pad42)") (class "Default")
      (node (ref "U3") (pin "42") (pinfunction "AREF_42") (pintype "bidirectional"))
    )
    (net (code "182") (name "unconnected-(U3-PB0(SS{slash}PCINT0)-Pad8)") (class "Default")
      (node (ref "U3") (pin "8") (pinfunction "PB0(SS/PCINT0)_8") (pintype "bidirectional"))
    )
    (net (code "183") (name "unconnected-(U3-PB4(PCINT4{slash}ADC11)-Pad28)") (class "Default")
      (node (ref "U3") (pin "28") (pinfunction "PB4(PCINT4/ADC11)_28") (pintype "bidirectional"))
    )
    (net (code "184") (name "unconnected-(U3-PB5(PCINT5(OC1A{slash}OC4B{slash}ADC12)-Pad29)") (class "Default")
      (node (ref "U3") (pin "29") (pinfunction "PB5(PCINT5(OC1A/OC4B/ADC12)_29") (pintype "bidirectional"))
    )
    (net (code "185") (name "unconnected-(U3-PB6(PCINT6{slash}OC1B{slash}OC4B{slash}ADC13)-Pad30)") (class "Default")
      (node (ref "U3") (pin "30") (pinfunction "PB6(PCINT6/OC1B/OC4B/ADC13)_30") (pintype "bidirectional"))
    )
    (net (code "186") (name "unconnected-(U3-PB7(PCINT7{slash}OC0A{slash}OC1C{slash}RTS)-Pad12)") (class "Default")
      (node (ref "U3") (pin "12") (pinfunction "PB7(PCINT7/OC0A/OC1C/RTS)_12") (pintype "bidirectional"))
    )
    (net (code "187") (name "unconnected-(U3-PC6(OC3A{slash}OC4A)-Pad31)") (class "Default")
      (node (ref "U3") (pin "31") (pinfunction "PC6(OC3A/OC4A)_31") (pintype "bidirectional"))
    )
    (net (code "188") (name "unconnected-(U3-PC7(ICP3{slash}CLK0{slash}OC4A)-Pad32)") (class "Default")
      (node (ref "U3") (pin "32") (pinfunction "PC7(ICP3/CLK0/OC4A)_32") (pintype "bidirectional"))
    )
    (net (code "189") (name "unconnected-(U3-PD4(ICP1{slash}ADC8)-Pad25)") (class "Default")
      (node (ref "U3") (pin "25") (pinfunction "PD4(ICP1/ADC8)_25") (pintype "bidirectional"))
    )
    (net (code "190") (name "unconnected-(U3-PD5(XCK1{slash}CTS)-Pad22)") (class "Default")
      (node (ref "U3") (pin "22") (pinfunction "PD5(XCK1/CTS)_22") (pintype "bidirectional"))
    )
    (net (code "191") (name "unconnected-(U3-PD6(T1{slash}OC4D{slash}ADC9)-Pad26)") (class "Default")
      (node (ref "U3") (pin "26") (pinfunction "PD6(T1/OC4D/ADC9)_26") (pintype "bidirectional"))
    )
    (net (code "192") (name "unconnected-(U3-PD7(T0{slash}OC4D{slash}ADC10)-Pad27)") (class "Default")
      (node (ref "U3") (pin "27") (pinfunction "PD7(T0/OC4D/ADC10)_27") (pintype "bidirectional"))
    )
    (net (code "193") (name "unconnected-(U3-PF0(ADC0)-Pad41)") (class "Default")
      (node (ref "U3") (pin "41") (pinfunction "PF0(ADC0)_41") (pintype "bidirectional"))
    )
    (net (code "194") (name "unconnected-(U3-PF1(ADC1)-Pad40)") (class "Default")
      (node (ref "U3") (pin "40") (pinfunction "PF1(ADC1)_40") (pintype "bidirectional"))
    )
    (net (code "195") (name "unconnected-(U3-PF4(ADC4{slash}TCK)-Pad39)") (class "Default")
      (node (ref "U3") (pin "39") (pinfunction "PF4(ADC4/TCK)_39") (pintype "bidirectional"))
    )
    (net (code "196") (name "unconnected-(U3-PF5(ADC5{slash}TMS)-Pad38)") (class "Default")
      (node (ref "U3") (pin "38") (pinfunction "PF5(ADC5/TMS)_38") (pintype "bidirectional"))
    )
    (net (code "197") (name "unconnected-(U3-PF6(ADC6{slash}TDO)-Pad37)") (class "Default")
      (node (ref "U3") (pin "37") (pinfunction "PF6(ADC6/TDO)_37") (pintype "bidirectional"))
    )
    (net (code "198") (name "unconnected-(U3-PF7(ADC7{slash}TDI)-Pad36)") (class "Default")
      (node (ref "U3") (pin "36") (pinfunction "PF7(ADC7/TDI)_36") (pintype "bidirectional"))
    )
    (net (code "199") (name "unconnected-(U5-IO_25_14-PadM10)") (class "Default")
      (node (ref "U5") (pin "M10") (pinfunction "IO_25_14_M10") (pintype "bidirectional"))
    )
    (net (code "200") (name "unconnected-(U5-IO_25_34-PadL5)") (class "Default")
      (node (ref "U5") (pin "L5") (pinfunction "IO_25_34_L5") (pintype "bidirectional"))
    )
    (net (code "201") (name "unconnected-(U5-IO_L6P_T0_34-PadC5)") (class "Default")
      (node (ref "U5") (pin "C5") (pinfunction "IO_L6P_T0_34_C5") (pintype "bidirectional"))
    )
    (net (code "202") (name "unconnected-(U5-IO_L7N_T1_34-PadD4)") (class "Default")
      (node (ref "U5") (pin "D4") (pinfunction "IO_L7N_T1_34_D4") (pintype "bidirectional"))
    )
    (net (code "203") (name "unconnected-(U5-IO_L7P_T1_34-PadE4)") (class "Default")
      (node (ref "U5") (pin "E4") (pinfunction "IO_L7P_T1_34_E4") (pintype "bidirectional"))
    )
    (net (code "204") (name "unconnected-(U5-IO_L12N_T1_MRCC_34-PadF4)") (class "Default")
      (node (ref "U5") (pin "F4") (pinfunction "IO_L12N_T1_MRCC_34_F4") (pintype "bidirectional"))
    )
    (net (code "205") (name "unconnected-(U5-IO_L12P_T1_MRCC_34-PadG4)") (class "Default")
      (node (ref "U5") (pin "G4") (pinfunction "IO_L12P_T1_MRCC_34_G4") (pintype "bidirectional"))
    )
    (net (code "206") (name "unconnected-(U5-IO_L15P_T2_DQS_34-PadJ2)") (class "Default")
      (node (ref "U5") (pin "J2") (pinfunction "IO_L15P_T2_DQS_34_J2") (pintype "bidirectional"))
    )
    (net (code "207") (name "unconnected-(U5-IO_L16N_T2_34-PadK3)") (class "Default")
      (node (ref "U5") (pin "K3") (pinfunction "IO_L16N_T2_34_K3") (pintype "bidirectional"))
    )
    (net (code "208") (name "unconnected-(U5-IO_L16P_T2_34-PadK4)") (class "Default")
      (node (ref "U5") (pin "K4") (pinfunction "IO_L16P_T2_34_K4") (pintype "bidirectional"))
    )
    (net (code "209") (name "unconnected-(U5-IO_L17N_T2_34-PadJ3)") (class "Default")
      (node (ref "U5") (pin "J3") (pinfunction "IO_L17N_T2_34_J3") (pintype "bidirectional"))
    )
    (net (code "210") (name "unconnected-(U7-ALERT#-Pad7)") (class "Default")
      (node (ref "U7") (pin "7") (pinfunction "ALERT#_7") (pintype "bidirectional"))
    )
    (net (code "211") (name "unconnected-(U8-ALERT#-Pad7)") (class "Default")
      (node (ref "U8") (pin "7") (pinfunction "ALERT#_7") (pintype "bidirectional"))
    )
    (net (code "212") (name "unconnected-(U9-ALERT#-Pad7)") (class "Default")
      (node (ref "U9") (pin "7") (pinfunction "ALERT#_7") (pintype "bidirectional"))
    )
    (net (code "213") (name "unconnected-(U10-ALERT#-Pad7)") (class "Default")
      (node (ref "U10") (pin "7") (pinfunction "ALERT#_7") (pintype "bidirectional"))
    )
    (net (code "214") (name "unconnected-(U11-RUN2-Pad7)") (class "Default")
      (node (ref "U11") (pin "7") (pinfunction "RUN2_7") (pintype "bidirectional"))
    )
    (net (code "215") (name "unconnected-(U11-SW2-Pad6)") (class "Default")
      (node (ref "U11") (pin "6") (pinfunction "SW2_6") (pintype "bidirectional"))
    )
    (net (code "216") (name "unconnected-(U11-VFB2-Pad8)") (class "Default")
      (node (ref "U11") (pin "8") (pinfunction "VFB2_8") (pintype "bidirectional"))
    )
  )
)
